# INV_Power.net
KiCad netlist of a schematic drawn in Altium Designer
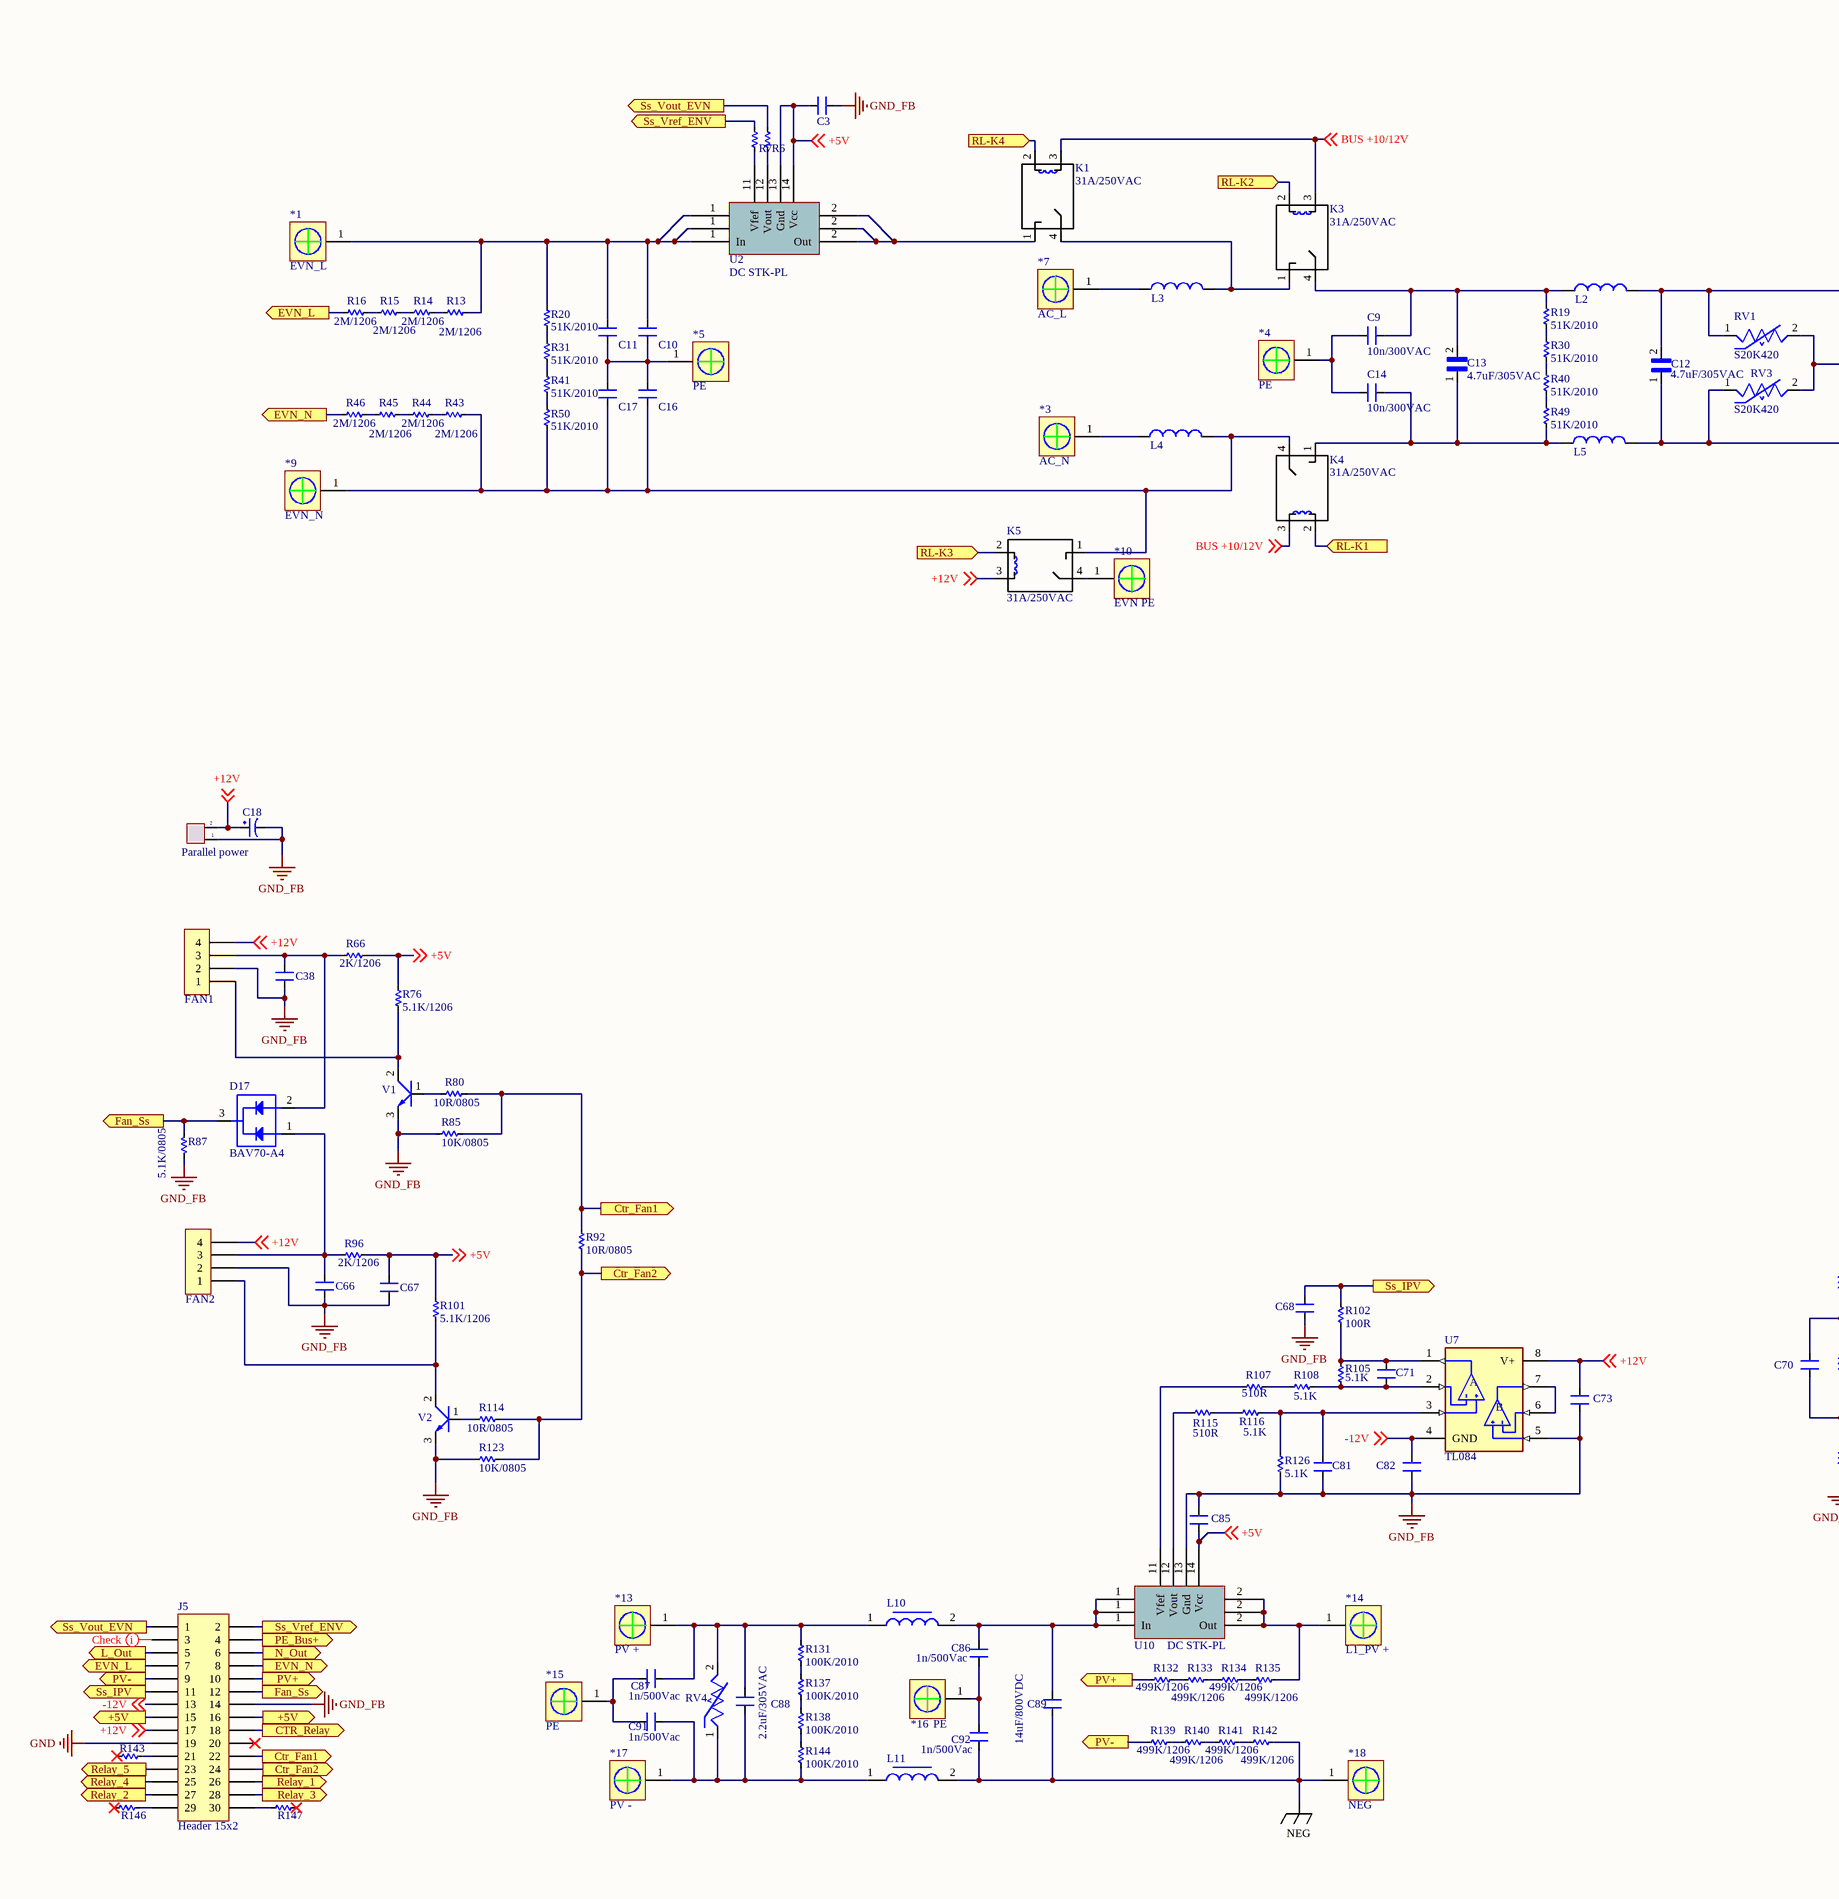
[diagram p0: INV.Power.SchDoc, left]
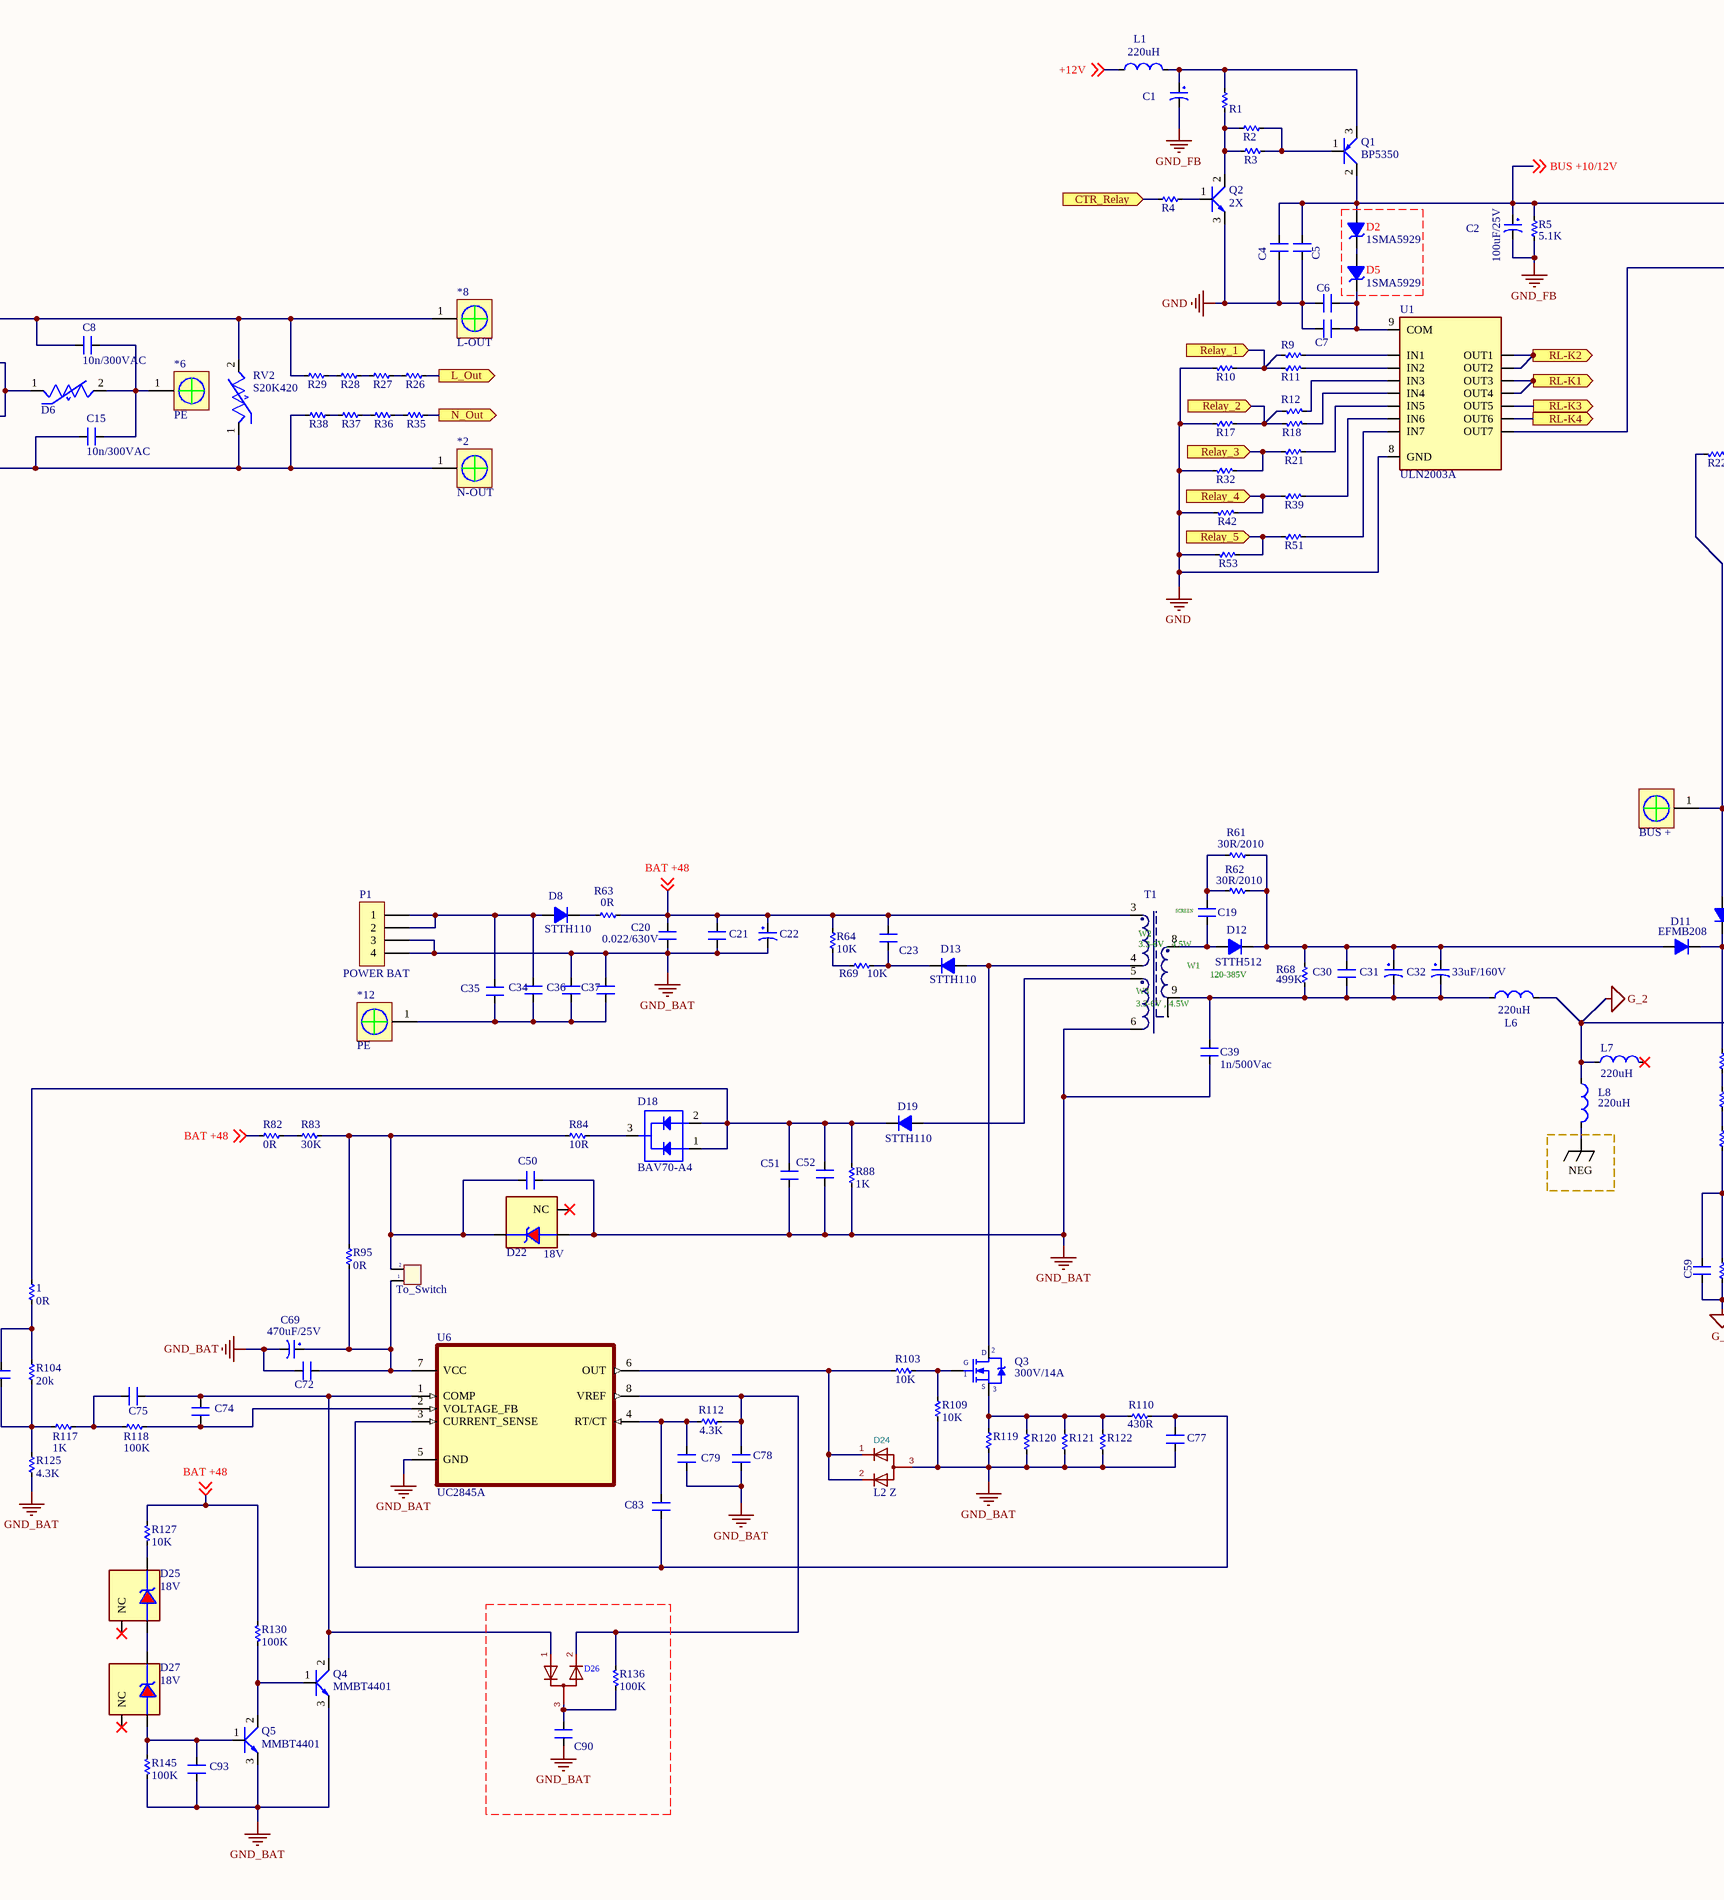
[diagram p1: INV.Power.SchDoc, middle]
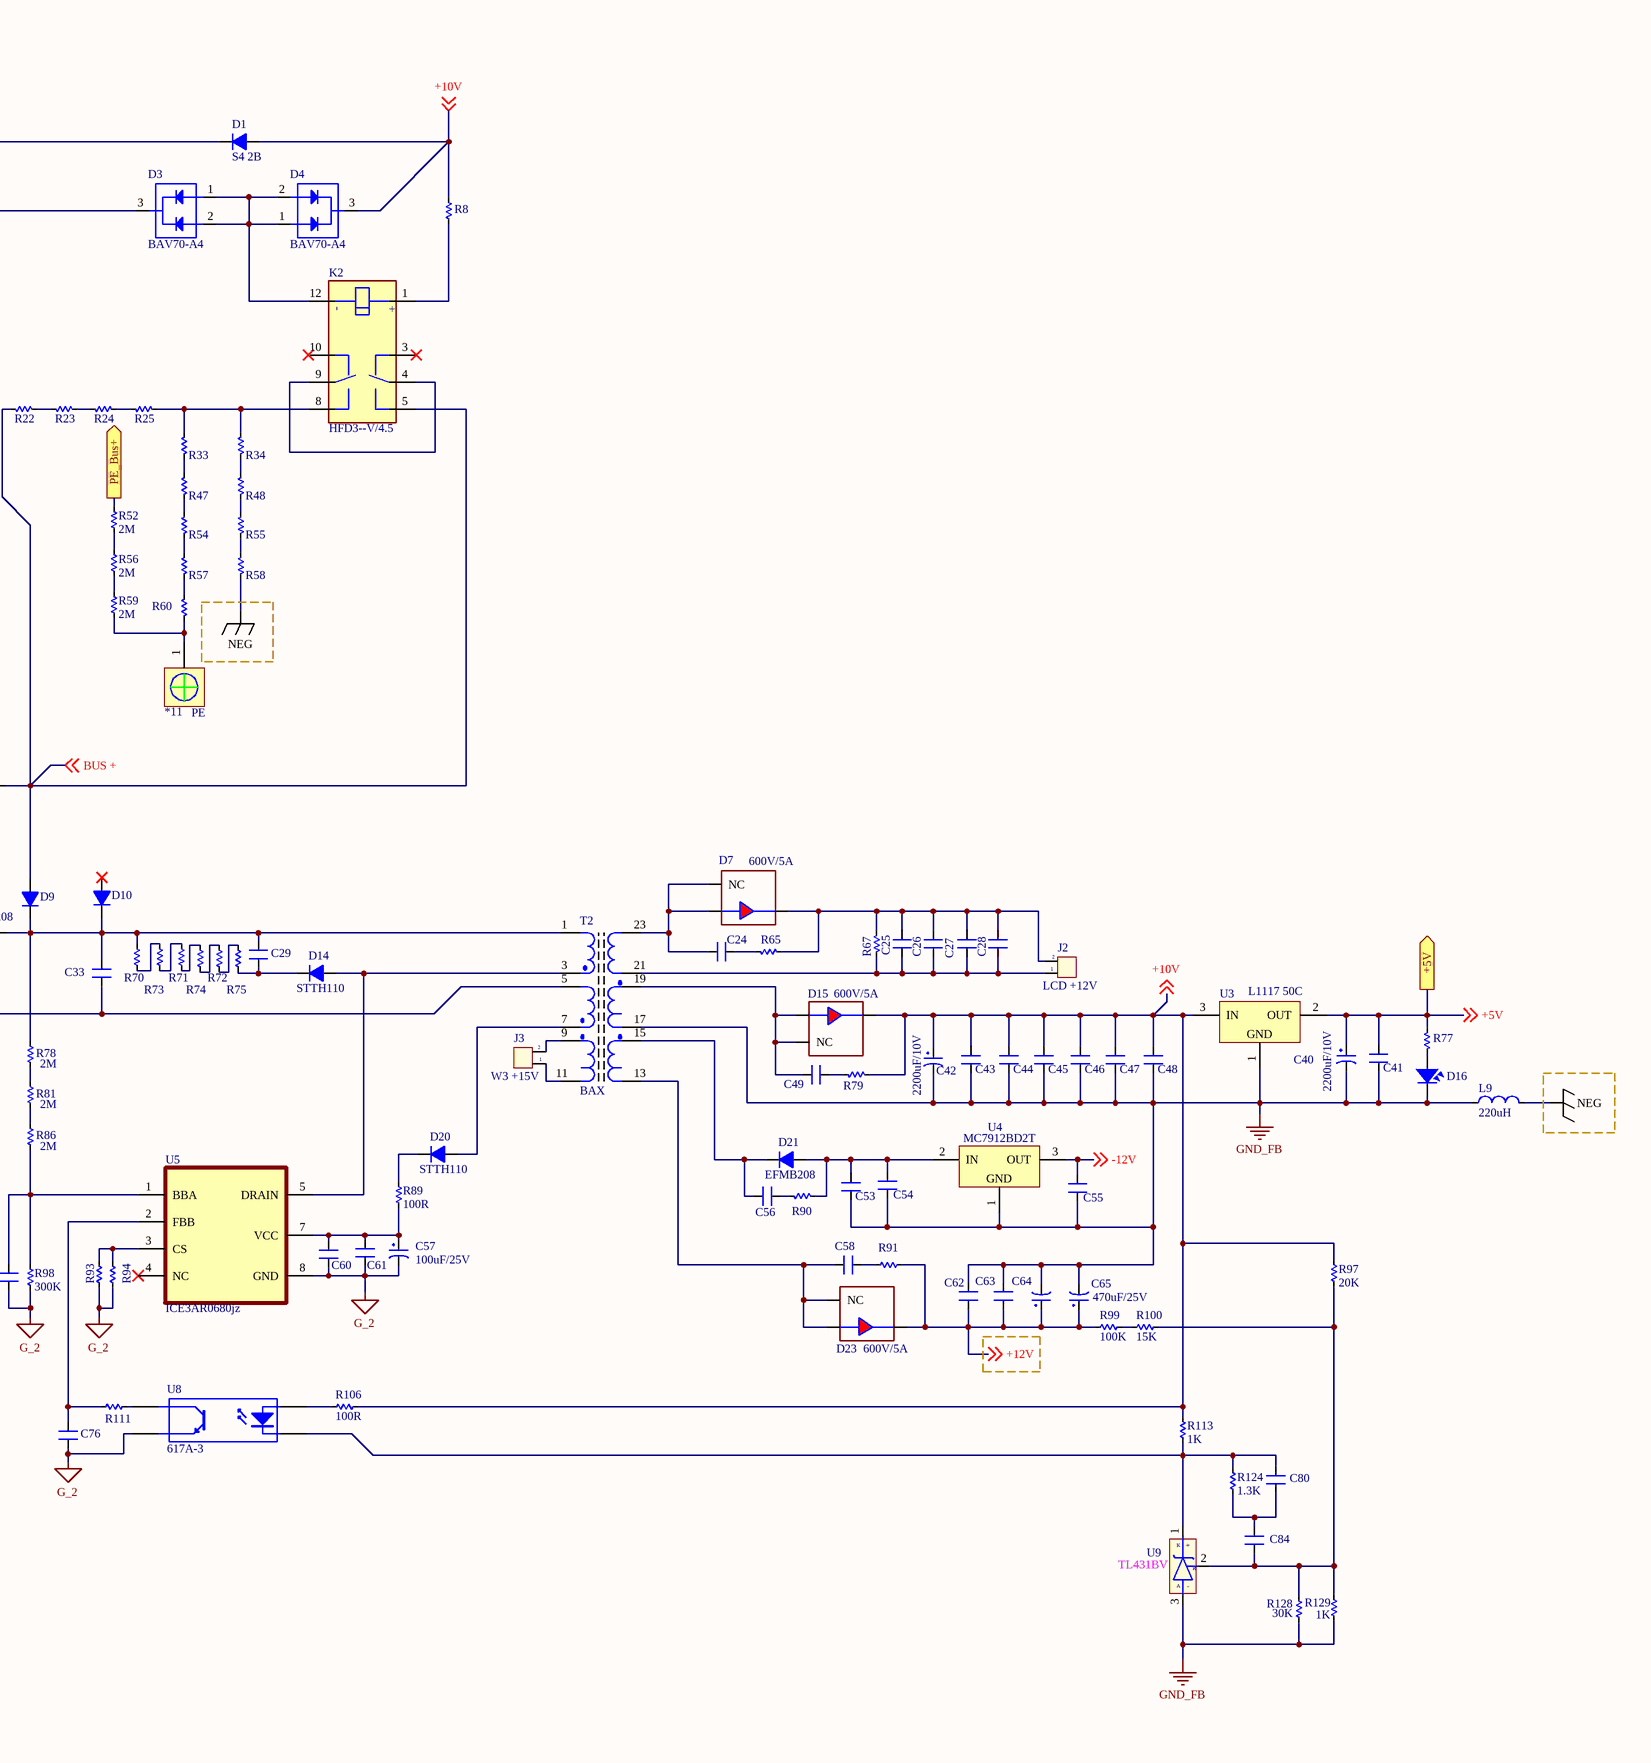
[diagram p2: INV.Power.SchDoc, right]

(export (version "E")
  (design (tool "Eeschema 10.0.6"))
  (components
    (comp (ref "*1") (value "EVN_L") (footprint "Copper Pipe") (libsource (lib "") (part "Copper_3")))
    (comp (ref "*2") (value "N-OUT") (footprint "Copper Pipe") (libsource (lib "") (part "Copper_2")))
    (comp (ref "*3") (value "AC_N") (footprint "Copper Pipe") (libsource (lib "") (part "Copper_1")))
    (comp (ref "*4") (value "PE") (footprint "Copper Pipe") (libsource (lib "") (part "Copper_1")))
    (comp (ref "*5") (value "PE") (footprint "Copper Pipe") (libsource (lib "Lib_RD_Cg") (part "Copper")))
    (comp (ref "*6") (value "PE") (footprint "Copper Pipe") (libsource (lib "") (part "Copper_2")))
    (comp (ref "*7") (value "AC_L") (footprint "Copper Pipe") (libsource (lib "") (part "Copper_1")))
    (comp (ref "*8") (value "L-OUT") (footprint "Copper Pipe") (libsource (lib "") (part "Copper_2")))
    (comp (ref "*9") (value "EVN_N") (footprint "Copper Pipe") (libsource (lib "") (part "Copper_3")))
    (comp (ref "*10")
      (value "EVN PE")
      (footprint "Copper Pipe")
      (libsource (lib "Lib_RD_Cg") (part "Copper"))
    )
    (comp (ref "*11") (value "PE") (footprint "Copper Pipe") (libsource (lib "") (part "Copper_3")))
    (comp (ref "*12") (value "PE") (footprint "Copper Pipe") (libsource (lib "") (part "Copper_1")))
    (comp (ref "*13") (value "PV +") (footprint "Copper Pipe") (libsource (lib "") (part "Copper_1")))
    (comp (ref "*14")
      (value "L1_PV +")
      (footprint "Copper Pipe")
      (libsource (lib "Lib_RD_Cg") (part "Copper"))
    )
    (comp (ref "*15") (value "PE") (footprint "Copper Pipe") (libsource (lib "") (part "Copper_1")))
    (comp (ref "*16") (value "PE") (footprint "Copper Pipe") (libsource (lib "") (part "Copper_1")))
    (comp (ref "*17") (value "PV -") (footprint "Copper Pipe") (libsource (lib "") (part "Copper_1")))
    (comp (ref "*18") (value "NEG") (footprint "Copper Pipe") (libsource (lib "Lib_RD_Cg") (part "Copper")))
    (comp (ref "1")
      (value "0R")
      (footprint "RES-SMD-0603 EX")
      (description "Resistor")
      (fields
        (field (name "MANUFACTURER") "Generic Components")
        (field (name "PUBLISHER") "Altium Hobart Technology Centre")
      )
      (libsource (lib "RAL") (part "Res-SMD"))
    )
    (comp (ref "C1")
      (value "100uF/25V")
      (footprint "CAP-10X17-N")
      (libsource (lib "Lib_RD_Cg") (part "Cap - 10x18 - N"))
    )
    (comp (ref "C2")
      (value "100uF/25V")
      (footprint "CAP-10X17-N")
      (libsource (lib "Lib_RD_Cg") (part "Cap - 10x18 - N"))
    )
    (comp (ref "C3")
      (value "10n/300VAC")
      (footprint "CAP-SMD-0805 EX")
      (description "High Voltage Ceramic Capacitors CS103M")
      (libsource (lib "RAL") (part "CAP-SMD"))
    )
    (comp (ref "C4") (value "~") (footprint "CAP-SMD-0805 EX") (libsource (lib "RAL") (part "CAP-SMD")))
    (comp (ref "C5") (value "~") (footprint "CAP-SMD-0805 EX") (libsource (lib "RAL") (part "CAP-SMD")))
    (comp (ref "C6") (value "~") (footprint "CAP-SMD-0805 EX") (libsource (lib "RAL") (part "CAP-SMD")))
    (comp (ref "C7") (value "~") (footprint "CAP-SMD-0805 EX") (libsource (lib "RAL") (part "CAP-SMD")))
    (comp (ref "C8")
      (value "10n/300VAC")
      (footprint "CAP-SMD-0805 EX")
      (description "High Voltage Ceramic Capacitors CS103M")
      (libsource (lib "RAL") (part "CAP-SMD"))
    )
    (comp (ref "C9")
      (value "10n/300VAC")
      (footprint "CAP-SMD-0805 EX")
      (description "High Voltage Ceramic Capacitors CS103M")
      (libsource (lib "RAL") (part "CAP-SMD"))
    )
    (comp (ref "C10")
      (value "10n/300VAC")
      (footprint "CAP-SMD-0805 EX")
      (description "High Voltage Ceramic Capacitors CS103M")
      (libsource (lib "RAL") (part "CAP-SMD"))
    )
    (comp (ref "C11")
      (value "10n/300VAC")
      (footprint "CAP-SMD-0805 EX")
      (description "High Voltage Ceramic Capacitors CS103M")
      (libsource (lib "RAL") (part "CAP-SMD"))
    )
    (comp (ref "C12")
      (value "4.7uF/305VAC")
      (footprint "CAPRR2250W80L2600T850H1500")
      (description "Polypropylene Film Capacitor, 305V ac, ±20%, 4.7μF")
      (fields (field (name "MP") "ECWFG2J475KA") (field (name "MF") "Panasonic"))
      (libsource (lib "Lib_RD_Cg") (part "ECWFG2J475KA"))
    )
    (comp (ref "C13")
      (value "4.7uF/305VAC")
      (footprint "CAPRR2250W80L2600T850H1500")
      (description "Polypropylene Film Capacitor, 305V ac, ±20%, 4.7μF")
      (fields (field (name "MP") "ECWFG2J475KA") (field (name "MF") "Panasonic"))
      (libsource (lib "Lib_RD_Cg") (part "ECWFG2J475KA"))
    )
    (comp (ref "C14")
      (value "10n/300VAC")
      (footprint "CAP-SMD-0805 EX")
      (description "High Voltage Ceramic Capacitors CS103M")
      (libsource (lib "RAL") (part "CAP-SMD"))
    )
    (comp (ref "C15")
      (value "10n/300VAC")
      (footprint "CAP-SMD-0805 EX")
      (description "High Voltage Ceramic Capacitors CS103M")
      (libsource (lib "RAL") (part "CAP-SMD"))
    )
    (comp (ref "C16")
      (value "10n/300VAC")
      (footprint "CAP-SMD-0805 EX")
      (description "High Voltage Ceramic Capacitors CS103M")
      (libsource (lib "RAL") (part "CAP-SMD"))
    )
    (comp (ref "C17")
      (value "10n/300VAC")
      (footprint "CAP-SMD-0805 EX")
      (description "High Voltage Ceramic Capacitors CS103M")
      (libsource (lib "RAL") (part "CAP-SMD"))
    )
    (comp (ref "C18")
      (value "470uF/25V")
      (footprint "CAP-10X17-N")
      (libsource (lib "") (part "Cap - 10x18 - N_2"))
    )
    (comp (ref "C19") (value "~") (footprint "CAP-SMD-0805 EX") (libsource (lib "RAL") (part "CAP-SMD")))
    (comp (ref "C20")
      (value "0.022/630V")
      (footprint "CAP-SMD-0805 EX")
      (description "WIMA MKS 4 Metallized Polyester (PET) Capacitors")
      (libsource (lib "RAL") (part "CAP-SMD"))
    )
    (comp (ref "C21") (value "~") (footprint "CAP-SMD-0805 EX") (libsource (lib "RAL") (part "CAP-SMD")))
    (comp (ref "C22")
      (value "27uF/100V")
      (footprint "CAP-10X17-N")
      (description "Cắm 100uF 25V")
      (libsource (lib "") (part "Cap - 10x18 - N_1"))
    )
    (comp (ref "C23") (value "~") (footprint "CAP-SMD-0805 EX") (libsource (lib "RAL") (part "CAP-SMD")))
    (comp (ref "C24") (value "~") (footprint "CAP-SMD-0805 EX") (libsource (lib "RAL") (part "CAP-SMD")))
    (comp (ref "C25")
      (value "223J630V")
      (footprint "CAP-SMD-0805 EX")
      (libsource (lib "RAL") (part "CAP-SMD"))
    )
    (comp (ref "C26")
      (value "223J630V")
      (footprint "CAP-SMD-0805 EX")
      (libsource (lib "RAL") (part "CAP-SMD"))
    )
    (comp (ref "C27")
      (value "223J630V")
      (footprint "CAP-SMD-0805 EX")
      (libsource (lib "RAL") (part "CAP-SMD"))
    )
    (comp (ref "C28")
      (value "223J630V")
      (footprint "CAP-SMD-0805 EX")
      (libsource (lib "RAL") (part "CAP-SMD"))
    )
    (comp (ref "C29")
      (value "223J630V")
      (footprint "CAP-SMD-0805 EX")
      (libsource (lib "RAL") (part "CAP-SMD"))
    )
    (comp (ref "C30") (value "~") (footprint "CAP-SMD-0805 EX") (libsource (lib "RAL") (part "CAP-SMD")))
    (comp (ref "C31")
      (value "33uF/160V")
      (footprint "CAP-10X17-N")
      (libsource (lib "") (part "Cap - 10x18 - N_1"))
    )
    (comp (ref "C32")
      (value "33uF/160V")
      (footprint "CAP-10X17-N")
      (libsource (lib "") (part "Cap - 10x18 - N_1"))
    )
    (comp (ref "C33")
      (value "2uF/600VDC")
      (footprint "CAP-SMD-0805 EX")
      (libsource (lib "RAL") (part "CAP-SMD"))
    )
    (comp (ref "C34") (value "~") (footprint "CAP-SMD-0805 EX") (libsource (lib "RAL") (part "CAP-SMD")))
    (comp (ref "C35") (value "~") (footprint "CAP-SMD-0805 EX") (libsource (lib "RAL") (part "CAP-SMD")))
    (comp (ref "C36") (value "~") (footprint "CAP-SMD-0805 EX") (libsource (lib "RAL") (part "CAP-SMD")))
    (comp (ref "C37") (value "~") (footprint "CAP-SMD-0805 EX") (libsource (lib "RAL") (part "CAP-SMD")))
    (comp (ref "C38") (value "~") (footprint "CAP-SMD-0805 EX") (libsource (lib "RAL") (part "CAP-SMD")))
    (comp (ref "C39")
      (value "1n/500Vac")
      (footprint "CAP-SMD-0805 EX")
      (libsource (lib "RAL") (part "CAP-SMD"))
    )
    (comp (ref "C40")
      (value "2200uF/10V")
      (footprint "CAP-10X17-N")
      (libsource (lib "") (part "Cap - 10x18 - N_1"))
    )
    (comp (ref "C41") (value "~") (footprint "CAP-SMD-0805 EX") (libsource (lib "RAL") (part "CAP-SMD")))
    (comp (ref "C42")
      (value "2200uF/10V")
      (footprint "CAP-10X17-N")
      (libsource (lib "") (part "Cap - 10x18 - N_1"))
    )
    (comp (ref "C43") (value "~") (footprint "CAP-SMD-0805 EX") (libsource (lib "RAL") (part "CAP-SMD")))
    (comp (ref "C44") (value "~") (footprint "CAP-SMD-0805 EX") (libsource (lib "RAL") (part "CAP-SMD")))
    (comp (ref "C45") (value "~") (footprint "CAP-SMD-0805 EX") (libsource (lib "RAL") (part "CAP-SMD")))
    (comp (ref "C46") (value "~") (footprint "CAP-SMD-0805 EX") (libsource (lib "RAL") (part "CAP-SMD")))
    (comp (ref "C47") (value "~") (footprint "CAP-SMD-0805 EX") (libsource (lib "RAL") (part "CAP-SMD")))
    (comp (ref "C48") (value "~") (footprint "CAP-SMD-0805 EX") (libsource (lib "RAL") (part "CAP-SMD")))
    (comp (ref "C49") (value "~") (footprint "CAP-SMD-0805 EX") (libsource (lib "RAL") (part "CAP-SMD")))
    (comp (ref "C50") (value "~") (footprint "CAP-SMD-0805 EX") (libsource (lib "RAL") (part "CAP-SMD")))
    (comp (ref "C51") (value "~") (footprint "CAP-SMD-0805 EX") (libsource (lib "RAL") (part "CAP-SMD")))
    (comp (ref "C52") (value "~") (footprint "CAP-SMD-0805 EX") (libsource (lib "RAL") (part "CAP-SMD")))
    (comp (ref "C53") (value "~") (footprint "CAP-SMD-0805 EX") (libsource (lib "RAL") (part "CAP-SMD")))
    (comp (ref "C54") (value "~") (footprint "CAP-SMD-0805 EX") (libsource (lib "RAL") (part "CAP-SMD")))
    (comp (ref "C55") (value "~") (footprint "CAP-SMD-0805 EX") (libsource (lib "RAL") (part "CAP-SMD")))
    (comp (ref "C56") (value "~") (footprint "CAP-SMD-0805 EX") (libsource (lib "RAL") (part "CAP-SMD")))
    (comp (ref "C57")
      (value "100uF/25V")
      (footprint "CAP-10X17-N")
      (description "Cắm 100uF 25V")
      (libsource (lib "") (part "Cap - 10x18 - N_1"))
    )
    (comp (ref "C58") (value "~") (footprint "CAP-SMD-0805 EX") (libsource (lib "RAL") (part "CAP-SMD")))
    (comp (ref "C59") (value "~") (footprint "CAP-SMD-0805 EX") (libsource (lib "RAL") (part "CAP-SMD")))
    (comp (ref "C60")
      (value "223J630V")
      (footprint "CAP-SMD-0805 EX")
      (libsource (lib "RAL") (part "CAP-SMD"))
    )
    (comp (ref "C61")
      (value "223J630V")
      (footprint "CAP-SMD-0805 EX")
      (libsource (lib "RAL") (part "CAP-SMD"))
    )
    (comp (ref "C62") (value "~") (footprint "CAP-SMD-0805 EX") (libsource (lib "RAL") (part "CAP-SMD")))
    (comp (ref "C63") (value "~") (footprint "CAP-SMD-0805 EX") (libsource (lib "RAL") (part "CAP-SMD")))
    (comp (ref "C64")
      (value "470uF/25V")
      (footprint "CAP-10X17-N")
      (libsource (lib "Lib_RD_Cg") (part "Cap - 10x18 - N"))
    )
    (comp (ref "C65")
      (value "470uF/25V")
      (footprint "CAP-10X17-N")
      (libsource (lib "Lib_RD_Cg") (part "Cap - 10x18 - N"))
    )
    (comp (ref "C66") (value "~") (footprint "CAP-SMD-0805 EX") (libsource (lib "RAL") (part "CAP-SMD")))
    (comp (ref "C67") (value "~") (footprint "CAP-SMD-0805 EX") (libsource (lib "RAL") (part "CAP-SMD")))
    (comp (ref "C68") (value "~") (footprint "CAP-SMD-0805 EX") (libsource (lib "RAL") (part "CAP-SMD")))
    (comp (ref "C69")
      (value "470uF/25V")
      (footprint "CAP-10X17-N")
      (description "Cắm 100uF 25V")
      (libsource (lib "") (part "Cap - 10x18 - N_3"))
    )
    (comp (ref "C70") (value "~") (footprint "CAP-SMD-0805 EX") (libsource (lib "RAL") (part "CAP-SMD")))
    (comp (ref "C71") (value "~") (footprint "CAP-SMD-0805 EX") (libsource (lib "RAL") (part "CAP-SMD")))
    (comp (ref "C72") (value "~") (footprint "CAP-SMD-0805 EX") (libsource (lib "RAL") (part "CAP-SMD")))
    (comp (ref "C73") (value "~") (footprint "CAP-SMD-0805 EX") (libsource (lib "RAL") (part "CAP-SMD")))
    (comp (ref "C74") (value "~") (footprint "CAP-SMD-0805 EX") (libsource (lib "RAL") (part "CAP-SMD")))
    (comp (ref "C75") (value "~") (footprint "CAP-SMD-0805 EX") (libsource (lib "RAL") (part "CAP-SMD")))
    (comp (ref "C76") (value "~") (footprint "CAP-SMD-0805 EX") (libsource (lib "RAL") (part "CAP-SMD")))
    (comp (ref "C77") (value "~") (footprint "CAP-SMD-0805 EX") (libsource (lib "RAL") (part "CAP-SMD")))
    (comp (ref "C78") (value "~") (footprint "CAP-SMD-0805 EX") (libsource (lib "RAL") (part "CAP-SMD")))
    (comp (ref "C79") (value "~") (footprint "CAP-SMD-0805 EX") (libsource (lib "RAL") (part "CAP-SMD")))
    (comp (ref "C80") (value "~") (footprint "CAP-SMD-0805 EX") (libsource (lib "RAL") (part "CAP-SMD")))
    (comp (ref "C81") (value "~") (footprint "CAP-SMD-0805 EX") (libsource (lib "RAL") (part "CAP-SMD")))
    (comp (ref "C82") (value "~") (footprint "CAP-SMD-0805 EX") (libsource (lib "RAL") (part "CAP-SMD")))
    (comp (ref "C83") (value "~") (footprint "CAP-SMD-0805 EX") (libsource (lib "RAL") (part "CAP-SMD")))
    (comp (ref "C84") (value "~") (footprint "CAP-SMD-0805 EX") (libsource (lib "RAL") (part "CAP-SMD")))
    (comp (ref "C85") (value "~") (footprint "CAP-SMD-0805 EX") (libsource (lib "RAL") (part "CAP-SMD")))
    (comp (ref "C86")
      (value "1n/500Vac")
      (footprint "CAP-SMD-0805 EX")
      (libsource (lib "RAL") (part "CAP-SMD"))
    )
    (comp (ref "C87")
      (value "1n/500Vac")
      (footprint "CAP-SMD-0805 EX")
      (libsource (lib "RAL") (part "CAP-SMD"))
    )
    (comp (ref "C88")
      (value "2.2uF/305VAC")
      (footprint "CAP-SMD-0805 EX")
      (libsource (lib "RAL") (part "CAP-SMD"))
    )
    (comp (ref "C89")
      (value "14uF/800VDC")
      (footprint "CAP-SMD-0805 EX")
      (libsource (lib "RAL") (part "CAP-SMD"))
    )
    (comp (ref "C90") (value "~") (footprint "CAP-SMD-0805 EX") (libsource (lib "RAL") (part "CAP-SMD")))
    (comp (ref "C91")
      (value "1n/500Vac")
      (footprint "CAP-SMD-0805 EX")
      (libsource (lib "RAL") (part "CAP-SMD"))
    )
    (comp (ref "C92")
      (value "1n/500Vac")
      (footprint "CAP-SMD-0805 EX")
      (libsource (lib "RAL") (part "CAP-SMD"))
    )
    (comp (ref "C93") (value "~") (footprint "CAP-SMD-0805 EX") (libsource (lib "RAL") (part "CAP-SMD")))
    (comp (ref "D1") (value "S4 2B") (footprint "1N4148") (libsource (lib "Lib_RD_Cg") (part "DIODE")))
    (comp (ref "D2")
      (value "1SMA5929")
      (footprint "DIODE ZENNER SOD123 *")
      (description "Diode Zenner 15V")
      (libsource (lib "Lib_RD_Cg") (part "DIODE ZENNER"))
    )
    (comp (ref "D3")
      (value "BAV70-A4")
      (footprint "DIO_STTH2003CG-TR")
      (fields (field (name "MP") "STTH2003CG-TR"))
      (libsource (lib "Lib_RD_Cg") (part "Diode Double"))
    )
    (comp (ref "D4")
      (value "BAV70-A4")
      (footprint "DIO_STTH2003CG-TR")
      (fields (field (name "MP") "STTH2003CG-TR"))
      (libsource (lib "Lib_RD_Cg") (part "Diode Double"))
    )
    (comp (ref "D5")
      (value "1SMA5929")
      (footprint "DIODE ZENNER SOD123 *")
      (description "Diode Zenner 15V")
      (libsource (lib "Lib_RD_Cg") (part "DIODE ZENNER"))
    )
    (comp (ref "D6")
      (value "EPCOS")
      (footprint "VAR_B72220S0301K101")
      (description "Chống sét lan truyền B88069X4880S102(ví dụ)")
      (fields (field (name "MP") "B72220S0301K101") (field (name "MF") "TDK"))
      (libsource (lib "Lib_RD_Cg") (part "Varistor B772"))
    )
    (comp (ref "D7")
      (value "600V/5A")
      (footprint "SOT95P237X112-3N")
      (description "600V/5A Diode SHHT 506B")
      (fields (field (name "MF") "ON Semiconductor") (field (name "MP") "BZX84-C7V5"))
      (libsource (lib "Lib_RD_Cg") (part "Diode SHHT 506B"))
    )
    (comp (ref "D8")
      (value "STTH110")
      (footprint "1N4148")
      (description "Diode 1000V/1A SMB")
      (libsource (lib "Lib_RD_Cg") (part "DIODE"))
    )
    (comp (ref "D9")
      (value "EFMB208")
      (footprint "1N4148")
      (description "Diode 600V/2A SMB thay the ES2J")
      (libsource (lib "Lib_RD_Cg") (part "DIODE"))
    )
    (comp (ref "D10")
      (value "EFMB208")
      (footprint "1N4148")
      (description "Diode 600V/2A SMB thay the ES2J")
      (libsource (lib "Lib_RD_Cg") (part "DIODE"))
    )
    (comp (ref "D11")
      (value "EFMB208")
      (footprint "1N4148")
      (description "Diode 600V/2A SMB thay the ES2J")
      (libsource (lib "Lib_RD_Cg") (part "DIODE"))
    )
    (comp (ref "D12")
      (value "STTH512")
      (footprint "1N4148")
      (description "Diode 1200V/5A")
      (libsource (lib "Lib_RD_Cg") (part "DIODE"))
    )
    (comp (ref "D13")
      (value "STTH110")
      (footprint "1N4148")
      (description "Diode 1000V/1A SMB")
      (libsource (lib "Lib_RD_Cg") (part "DIODE"))
    )
    (comp (ref "D14")
      (value "STTH110")
      (footprint "1N4148")
      (description "Diode 1000V/1A SMB")
      (libsource (lib "Lib_RD_Cg") (part "DIODE"))
    )
    (comp (ref "D15")
      (value "600V/5A")
      (footprint "SOT95P237X112-3N")
      (description "600V/5A Diode SHHT 506B")
      (fields (field (name "MF") "ON Semiconductor") (field (name "MP") "BZX84-C7V5"))
      (libsource (lib "") (part "Diode SHHT 506B_1"))
    )
    (comp (ref "D16")
      (value "LED")
      (footprint "LED 2835 NEW")
      (description "LED Single colour Green and Red")
      (libsource (lib "Lib_RD_Cg") (part "LED"))
    )
    (comp (ref "D17")
      (value "BAV70-A4")
      (footprint "DIO_STTH2003CG-TR")
      (fields (field (name "MP") "STTH2003CG-TR"))
      (libsource (lib "Lib_RD_Cg") (part "Diode Double"))
    )
    (comp (ref "D18")
      (value "BAV70-A4")
      (footprint "DIO_STTH2003CG-TR")
      (fields (field (name "MP") "STTH2003CG-TR"))
      (libsource (lib "Lib_RD_Cg") (part "Diode Double"))
    )
    (comp (ref "D19")
      (value "STTH110")
      (footprint "1N4148")
      (description "Diode 1000V/1A SMB")
      (libsource (lib "Lib_RD_Cg") (part "DIODE"))
    )
    (comp (ref "D20")
      (value "STTH110")
      (footprint "1N4148")
      (description "Diode 1000V/1A SMB")
      (libsource (lib "Lib_RD_Cg") (part "DIODE"))
    )
    (comp (ref "D21")
      (value "EFMB208")
      (footprint "1N4148")
      (description "Diode 600V/2A SMB thay the ES2J")
      (libsource (lib "Lib_RD_Cg") (part "DIODE"))
    )
    (comp (ref "D22")
      (value "18V")
      (footprint "SOT95P237X112-3N")
      (description "BZX84-C18(Y6W) Zenner 18V thay the BZT52C18")
      (fields (field (name "MF") "ON Semiconductor") (field (name "MP") "BZX84-C7V5"))
      (libsource (lib "") (part "Diode Zener Sot-95_1"))
    )
    (comp (ref "D23")
      (value "600V/5A")
      (footprint "SOT95P237X112-3N")
      (description "600V/5A Diode SHHT 506B")
      (fields (field (name "MF") "ON Semiconductor") (field (name "MP") "BZX84-C7V5"))
      (libsource (lib "Lib_RD_Cg") (part "Diode SHHT 506B"))
    )
    (comp (ref "D24")
      (value "L2 Z")
      (footprint "SOT-23")
      (description "LBAS40-06LT1G\r\n S-LBAS40-06LT1G")
      (libsource (lib "Lib_RD_Cg") (part "Dual-Diode_CA"))
    )
    (comp (ref "D25")
      (value "18V")
      (footprint "SOT95P237X112-3N")
      (description "BZX84-C18(Y6W) Zenner 18V thay the BZT52C18")
      (fields (field (name "MF") "ON Semiconductor") (field (name "MP") "BZX84-C7V5"))
      (libsource (lib "Lib_RD_Cg") (part "Diode Zener Sot-95"))
    )
    (comp (ref "D26")
      (value "Dual-Diode_CA_1")
      (footprint "SOT-23")
      (description "BAT54S(D88) thay the BAV99:A7")
      (libsource (lib "Lib_RD_Cg") (part "Dual-Diode_CA_1"))
    )
    (comp (ref "D27")
      (value "18V")
      (footprint "SOT95P237X112-3N")
      (description "BZX84-C18(Y6W) Zenner 18V thay the BZT52C18")
      (fields (field (name "MF") "ON Semiconductor") (field (name "MP") "BZX84-C7V5"))
      (libsource (lib "Lib_RD_Cg") (part "Diode Zener Sot-95"))
    )
    (comp (ref "H1")
      (value "FAN1")
      (footprint "XH2.54M-4")
      (description "Cắm")
      (libsource (lib "Altium_Lib_by_KhueNguyenCreator") (part "Header 4P 2.54 Duc Thang"))
    )
    (comp (ref "H2")
      (value "FAN2")
      (footprint "XH2.54M-4")
      (description "Cắm")
      (libsource (lib "Altium_Lib_by_KhueNguyenCreator") (part "Header 4P 2.54 Duc Thang"))
    )
    (comp (ref "J1") (value "Parallel power") (footprint "Jump2") (libsource (lib "AE_RD") (part "Jump2")))
    (comp (ref "J2") (value "LCD +12V") (footprint "Jump2") (libsource (lib "") (part "Jump2_1")))
    (comp (ref "J3") (value "W3 +15V") (footprint "Jump2") (libsource (lib "AE_RD") (part "Jump2")))
    (comp (ref "J4") (value "To_Switch") (footprint "Jump2") (libsource (lib "") (part "Jump2_1")))
    (comp (ref "J5")
      (value "Header 15x2")
      (footprint "Head 1X16 - CAI THANG")
      (description "Header, 15x2-Pin 2.5mm")
      (fields (field (name "PUBLISHER") "Altium Limited"))
      (libsource (lib "Lib_RD_Cg") (part "Header 15x2"))
    )
    (comp (ref "K1")
      (value "31A/250VAC")
      (footprint "RELAY 10A/250V")
      (description "HF161F-W 12-HT(477)")
      (libsource (lib "Lib_RD_Cg") (part "RELAY 10A/250V-HF"))
    )
    (comp (ref "K2")
      (value "HFD3--V/4.5")
      (footprint "HFD3")
      (fields (field (name "MF") "Hongfa") (field (name "MP") "HFD3/012-L2"))
      (libsource (lib "Lib_RD_Cg") (part "HFD3--V/4.5"))
    )
    (comp (ref "K3")
      (value "31A/250VAC")
      (footprint "RELAY 10A/250V")
      (description "HF161F-W 12-HT(477)")
      (libsource (lib "Lib_RD_Cg") (part "RELAY 10A/250V-HF"))
    )
    (comp (ref "K4")
      (value "31A/250VAC")
      (footprint "RELAY 10A/250V")
      (description "HF161F-W 12-HT(477)")
      (libsource (lib "Lib_RD_Cg") (part "RELAY 10A/250V-HF"))
    )
    (comp (ref "K5")
      (value "31A/250VAC")
      (footprint "RELAY 10A/250V")
      (description "HF161F-W 12-HT(477)")
      (libsource (lib "") (part "RELAY 10A/250V-HF_1"))
    )
    (comp (ref "L1")
      (value "220uH")
      (footprint "CUON LOC 1010")
      (description "Inductor")
      (libsource (lib "") (part "L1_1"))
    )
    (comp (ref "L2")
      (value "Cuộn L")
      (footprint "IND_1210")
      (description "Fixed Inductors 18uH 10% 2.52MHz")
      (fields
        (field (name "MANUFACTURER") "Wurth Electronics")
        (field (name "MANUFACTURER PART NUMBER") "CMH322522-180KL")
      )
      (libsource (lib "Altium_Lib_by_KhueNguyenCreator") (part "IND_18uH-0.12A-10%-SMD"))
    )
    (comp (ref "L3")
      (value "Cuộn L")
      (footprint "IND_1210")
      (description "Fixed Inductors 18uH 10% 2.52MHz")
      (fields
        (field (name "MANUFACTURER") "Wurth Electronics")
        (field (name "MANUFACTURER PART NUMBER") "CMH322522-180KL")
      )
      (libsource (lib "Altium_Lib_by_KhueNguyenCreator") (part "IND_18uH-0.12A-10%-SMD"))
    )
    (comp (ref "L4")
      (value "Cuộn L")
      (footprint "IND_1210")
      (description "Fixed Inductors 18uH 10% 2.52MHz")
      (fields
        (field (name "MANUFACTURER") "Wurth Electronics")
        (field (name "MANUFACTURER PART NUMBER") "CMH322522-180KL")
      )
      (libsource (lib "Altium_Lib_by_KhueNguyenCreator") (part "IND_18uH-0.12A-10%-SMD"))
    )
    (comp (ref "L5")
      (value "Cuộn L")
      (footprint "IND_1210")
      (description "Fixed Inductors 18uH 10% 2.52MHz")
      (fields
        (field (name "MANUFACTURER") "Wurth Electronics")
        (field (name "MANUFACTURER PART NUMBER") "CMH322522-180KL")
      )
      (libsource (lib "Altium_Lib_by_KhueNguyenCreator") (part "IND_18uH-0.12A-10%-SMD"))
    )
    (comp (ref "L6")
      (value "220uH")
      (footprint "CUON LOC 1010")
      (description "Inductor")
      (libsource (lib "") (part "L1_1"))
    )
    (comp (ref "L7")
      (value "220uH")
      (footprint "CUON LOC 1010")
      (description "Inductor")
      (libsource (lib "Lib_RD_Cg") (part "L1"))
    )
    (comp (ref "L8")
      (value "220uH")
      (footprint "CUON LOC 1010")
      (description "Inductor")
      (libsource (lib "Lib_RD_Cg") (part "L1"))
    )
    (comp (ref "L9")
      (value "220uH")
      (footprint "CUON LOC 1010")
      (description "Inductor")
      (libsource (lib "") (part "L1_1"))
    )
    (comp (ref "L10")
      (value "L")
      (footprint "Cuan Cam PWM Hybrid")
      (description "Cuận cảm bộ sạc PWM Hybrid")
      (fields (field (name "DESIGNED BY") "VanDungEvn"))
      (libsource (lib "Lib_RD_Cg") (part "CUON CAM PWM Hybrid"))
    )
    (comp (ref "L11")
      (value "L")
      (footprint "Cuan Cam PWM Hybrid")
      (description "Cuận cảm bộ sạc PWM Hybrid")
      (fields (field (name "DESIGNED BY") "VanDungEvn"))
      (libsource (lib "Lib_RD_Cg") (part "CUON CAM PWM Hybrid"))
    )
    (comp (ref "P1")
      (value "POWER BAT")
      (footprint "XH2.54M-4")
      (description "Cắm")
      (libsource (lib "") (part "Header 4P 2.54 Duc Thang_1"))
    )
    (comp (ref "PV +1") (value "BUS +") (footprint "Copper Pipe") (libsource (lib "") (part "Copper_1")))
    (comp (ref "Q1")
      (value "BP5350")
      (footprint "QTO-92")
      (description "thay the B772")
      (libsource (lib "Lib_RD_Cg") (part "B772M-PNP"))
    )
    (comp (ref "Q2")
      (value "2X")
      (description "thay the MMPT2222 40V/06A")
      (libsource (lib "Lib_RD_Cg") (part "D882M"))
    )
    (comp (ref "Q3")
      (value "300V/14A")
      (footprint "TO220H1")
      (description "14N30")
      (libsource (lib "RAL") (part "MOSFET IRF N"))
    )
    (comp (ref "Q4") (value "MMBT4401") (description "NPN") (libsource (lib "Lib_RD_Cg") (part "D882M")))
    (comp (ref "Q5") (value "MMBT4401") (description "NPN") (libsource (lib "Lib_RD_Cg") (part "D882M")))
    (comp (ref "R1")
      (value "10K")
      (footprint "RES-SMD-0603 EX")
      (description "Resistor")
      (fields
        (field (name "MANUFACTURER") "Generic Components")
        (field (name "PUBLISHER") "Altium Hobart Technology Centre")
      )
      (libsource (lib "RAL") (part "Res-SMD"))
    )
    (comp (ref "R2")
      (value "2K")
      (footprint "RES-SMD-0603 EX")
      (description "Resistor")
      (fields
        (field (name "MANUFACTURER") "Generic Components")
        (field (name "PUBLISHER") "Altium Hobart Technology Centre")
      )
      (libsource (lib "RAL") (part "Res-SMD"))
    )
    (comp (ref "R3")
      (value "2K")
      (footprint "RES-SMD-0603 EX")
      (description "Resistor")
      (fields
        (field (name "MANUFACTURER") "Generic Components")
        (field (name "PUBLISHER") "Altium Hobart Technology Centre")
      )
      (libsource (lib "RAL") (part "Res-SMD"))
    )
    (comp (ref "R4")
      (value "20K")
      (footprint "RES-SMD-0603 EX")
      (description "Resistor")
      (fields
        (field (name "MANUFACTURER") "Generic Components")
        (field (name "PUBLISHER") "Altium Hobart Technology Centre")
      )
      (libsource (lib "RAL") (part "Res-SMD"))
    )
    (comp (ref "R5")
      (value "5.1K")
      (footprint "RES-SMD-0603 EX")
      (description "Resistor")
      (fields
        (field (name "MANUFACTURER") "Generic Components")
        (field (name "PUBLISHER") "Altium Hobart Technology Centre")
      )
      (libsource (lib "RAL") (part "Res-SMD"))
    )
    (comp (ref "R6")
      (value "1K/0603")
      (footprint "RES-SMD-0603 EX")
      (description "Resistor")
      (fields
        (field (name "MANUFACTURER") "Generic Components")
        (field (name "PUBLISHER") "Altium Hobart Technology Centre")
      )
      (libsource (lib "RAL") (part "Res-SMD"))
    )
    (comp (ref "R7")
      (value "1K/0603")
      (footprint "RES-SMD-0603 EX")
      (description "Resistor")
      (fields
        (field (name "MANUFACTURER") "Generic Components")
        (field (name "PUBLISHER") "Altium Hobart Technology Centre")
      )
      (libsource (lib "RAL") (part "Res-SMD"))
    )
    (comp (ref "R8")
      (value "51R")
      (footprint "RES-SMD-0603 EX")
      (description "Resistor")
      (fields
        (field (name "MANUFACTURER") "Generic Components")
        (field (name "PUBLISHER") "Altium Hobart Technology Centre")
      )
      (libsource (lib "RAL") (part "Res-SMD"))
    )
    (comp (ref "R9")
      (value "10R")
      (footprint "RES-SMD-0603 EX")
      (description "Resistor")
      (fields
        (field (name "MANUFACTURER") "Generic Components")
        (field (name "PUBLISHER") "Altium Hobart Technology Centre")
      )
      (libsource (lib "RAL") (part "Res-SMD"))
    )
    (comp (ref "R10")
      (value "5.1K")
      (footprint "RES-SMD-0603 EX")
      (description "Resistor")
      (fields
        (field (name "MANUFACTURER") "Generic Components")
        (field (name "PUBLISHER") "Altium Hobart Technology Centre")
      )
      (libsource (lib "RAL") (part "Res-SMD"))
    )
    (comp (ref "R11")
      (value "10R")
      (footprint "RES-SMD-0603 EX")
      (description "Resistor")
      (fields
        (field (name "MANUFACTURER") "Generic Components")
        (field (name "PUBLISHER") "Altium Hobart Technology Centre")
      )
      (libsource (lib "RAL") (part "Res-SMD"))
    )
    (comp (ref "R12")
      (value "10R")
      (footprint "RES-SMD-0603 EX")
      (description "Resistor")
      (fields
        (field (name "MANUFACTURER") "Generic Components")
        (field (name "PUBLISHER") "Altium Hobart Technology Centre")
      )
      (libsource (lib "RAL") (part "Res-SMD"))
    )
    (comp (ref "R13")
      (value "2M/1206")
      (footprint "RES-SMD-0603 EX")
      (description "Resistor")
      (fields
        (field (name "MANUFACTURER") "Generic Components")
        (field (name "PUBLISHER") "Altium Hobart Technology Centre")
      )
      (libsource (lib "RAL") (part "Res-SMD"))
    )
    (comp (ref "R14")
      (value "2M/1206")
      (footprint "RES-SMD-0603 EX")
      (description "Resistor")
      (fields
        (field (name "MANUFACTURER") "Generic Components")
        (field (name "PUBLISHER") "Altium Hobart Technology Centre")
      )
      (libsource (lib "RAL") (part "Res-SMD"))
    )
    (comp (ref "R15")
      (value "2M/1206")
      (footprint "RES-SMD-0603 EX")
      (description "Resistor")
      (fields
        (field (name "MANUFACTURER") "Generic Components")
        (field (name "PUBLISHER") "Altium Hobart Technology Centre")
      )
      (libsource (lib "RAL") (part "Res-SMD"))
    )
    (comp (ref "R16")
      (value "2M/1206")
      (footprint "RES-SMD-0603 EX")
      (description "Resistor")
      (fields
        (field (name "MANUFACTURER") "Generic Components")
        (field (name "PUBLISHER") "Altium Hobart Technology Centre")
      )
      (libsource (lib "RAL") (part "Res-SMD"))
    )
    (comp (ref "R17")
      (value "5.1K")
      (footprint "RES-SMD-0603 EX")
      (description "Resistor")
      (fields
        (field (name "MANUFACTURER") "Generic Components")
        (field (name "PUBLISHER") "Altium Hobart Technology Centre")
      )
      (libsource (lib "RAL") (part "Res-SMD"))
    )
    (comp (ref "R18")
      (value "10R")
      (footprint "RES-SMD-0603 EX")
      (description "Resistor")
      (fields
        (field (name "MANUFACTURER") "Generic Components")
        (field (name "PUBLISHER") "Altium Hobart Technology Centre")
      )
      (libsource (lib "RAL") (part "Res-SMD"))
    )
    (comp (ref "R19")
      (value "51K/2010")
      (footprint "RES-SMD-0603 EX")
      (description "Resistor")
      (fields
        (field (name "MANUFACTURER") "Generic Components")
        (field (name "PUBLISHER") "Altium Hobart Technology Centre")
      )
      (libsource (lib "RAL") (part "Res-SMD"))
    )
    (comp (ref "R20")
      (value "51K/2010")
      (footprint "RES-SMD-0603 EX")
      (description "Resistor")
      (fields
        (field (name "MANUFACTURER") "Generic Components")
        (field (name "PUBLISHER") "Altium Hobart Technology Centre")
      )
      (libsource (lib "RAL") (part "Res-SMD"))
    )
    (comp (ref "R21")
      (value "10R")
      (footprint "RES-SMD-0603 EX")
      (description "Resistor")
      (fields
        (field (name "MANUFACTURER") "Generic Components")
        (field (name "PUBLISHER") "Altium Hobart Technology Centre")
      )
      (libsource (lib "RAL") (part "Res-SMD"))
    )
    (comp (ref "R22")
      (value "499K")
      (footprint "RES-SMD-0603 EX")
      (description "Resistor")
      (fields
        (field (name "MANUFACTURER") "Generic Components")
        (field (name "PUBLISHER") "Altium Hobart Technology Centre")
      )
      (libsource (lib "RAL") (part "Res-SMD"))
    )
    (comp (ref "R23")
      (value "499K")
      (footprint "RES-SMD-0603 EX")
      (description "Resistor")
      (fields
        (field (name "MANUFACTURER") "Generic Components")
        (field (name "PUBLISHER") "Altium Hobart Technology Centre")
      )
      (libsource (lib "RAL") (part "Res-SMD"))
    )
    (comp (ref "R24")
      (value "499K")
      (footprint "RES-SMD-0603 EX")
      (description "Resistor")
      (fields
        (field (name "MANUFACTURER") "Generic Components")
        (field (name "PUBLISHER") "Altium Hobart Technology Centre")
      )
      (libsource (lib "RAL") (part "Res-SMD"))
    )
    (comp (ref "R25")
      (value "499K")
      (footprint "RES-SMD-0603 EX")
      (description "Resistor")
      (fields
        (field (name "MANUFACTURER") "Generic Components")
        (field (name "PUBLISHER") "Altium Hobart Technology Centre")
      )
      (libsource (lib "RAL") (part "Res-SMD"))
    )
    (comp (ref "R26")
      (value "2M/1206")
      (footprint "RES-SMD-0603 EX")
      (description "Resistor")
      (fields
        (field (name "MANUFACTURER") "Generic Components")
        (field (name "PUBLISHER") "Altium Hobart Technology Centre")
      )
      (libsource (lib "RAL") (part "Res-SMD"))
    )
    (comp (ref "R27")
      (value "2M/1206")
      (footprint "RES-SMD-0603 EX")
      (description "Resistor")
      (fields
        (field (name "MANUFACTURER") "Generic Components")
        (field (name "PUBLISHER") "Altium Hobart Technology Centre")
      )
      (libsource (lib "RAL") (part "Res-SMD"))
    )
    (comp (ref "R28")
      (value "2M/1206")
      (footprint "RES-SMD-0603 EX")
      (description "Resistor")
      (fields
        (field (name "MANUFACTURER") "Generic Components")
        (field (name "PUBLISHER") "Altium Hobart Technology Centre")
      )
      (libsource (lib "RAL") (part "Res-SMD"))
    )
    (comp (ref "R29")
      (value "2M/1206")
      (footprint "RES-SMD-0603 EX")
      (description "Resistor")
      (fields
        (field (name "MANUFACTURER") "Generic Components")
        (field (name "PUBLISHER") "Altium Hobart Technology Centre")
      )
      (libsource (lib "RAL") (part "Res-SMD"))
    )
    (comp (ref "R30")
      (value "51K/2010")
      (footprint "RES-SMD-0603 EX")
      (description "Resistor")
      (fields
        (field (name "MANUFACTURER") "Generic Components")
        (field (name "PUBLISHER") "Altium Hobart Technology Centre")
      )
      (libsource (lib "RAL") (part "Res-SMD"))
    )
    (comp (ref "R31")
      (value "51K/2010")
      (footprint "RES-SMD-0603 EX")
      (description "Resistor")
      (fields
        (field (name "MANUFACTURER") "Generic Components")
        (field (name "PUBLISHER") "Altium Hobart Technology Centre")
      )
      (libsource (lib "RAL") (part "Res-SMD"))
    )
    (comp (ref "R32")
      (value "5.1K")
      (footprint "RES-SMD-0603 EX")
      (description "Resistor")
      (fields
        (field (name "MANUFACTURER") "Generic Components")
        (field (name "PUBLISHER") "Altium Hobart Technology Centre")
      )
      (libsource (lib "RAL") (part "Res-SMD"))
    )
    (comp (ref "R33")
      (value "200K")
      (footprint "RES-SMD-0603 EX")
      (description "Resistor")
      (fields
        (field (name "MANUFACTURER") "Generic Components")
        (field (name "PUBLISHER") "Altium Hobart Technology Centre")
      )
      (libsource (lib "RAL") (part "Res-SMD"))
    )
    (comp (ref "R34")
      (value "499K")
      (footprint "RES-SMD-0603 EX")
      (description "Resistor")
      (fields
        (field (name "MANUFACTURER") "Generic Components")
        (field (name "PUBLISHER") "Altium Hobart Technology Centre")
      )
      (libsource (lib "RAL") (part "Res-SMD"))
    )
    (comp (ref "R35")
      (value "2M/1206")
      (footprint "RES-SMD-0603 EX")
      (description "Resistor")
      (fields
        (field (name "MANUFACTURER") "Generic Components")
        (field (name "PUBLISHER") "Altium Hobart Technology Centre")
      )
      (libsource (lib "RAL") (part "Res-SMD"))
    )
    (comp (ref "R36")
      (value "2M/1206")
      (footprint "RES-SMD-0603 EX")
      (description "Resistor")
      (fields
        (field (name "MANUFACTURER") "Generic Components")
        (field (name "PUBLISHER") "Altium Hobart Technology Centre")
      )
      (libsource (lib "RAL") (part "Res-SMD"))
    )
    (comp (ref "R37")
      (value "2M/1206")
      (footprint "RES-SMD-0603 EX")
      (description "Resistor")
      (fields
        (field (name "MANUFACTURER") "Generic Components")
        (field (name "PUBLISHER") "Altium Hobart Technology Centre")
      )
      (libsource (lib "RAL") (part "Res-SMD"))
    )
    (comp (ref "R38")
      (value "2M/1206")
      (footprint "RES-SMD-0603 EX")
      (description "Resistor")
      (fields
        (field (name "MANUFACTURER") "Generic Components")
        (field (name "PUBLISHER") "Altium Hobart Technology Centre")
      )
      (libsource (lib "RAL") (part "Res-SMD"))
    )
    (comp (ref "R39")
      (value "10R")
      (footprint "RES-SMD-0603 EX")
      (description "Resistor")
      (fields
        (field (name "MANUFACTURER") "Generic Components")
        (field (name "PUBLISHER") "Altium Hobart Technology Centre")
      )
      (libsource (lib "RAL") (part "Res-SMD"))
    )
    (comp (ref "R40")
      (value "51K/2010")
      (footprint "RES-SMD-0603 EX")
      (description "Resistor")
      (fields
        (field (name "MANUFACTURER") "Generic Components")
        (field (name "PUBLISHER") "Altium Hobart Technology Centre")
      )
      (libsource (lib "RAL") (part "Res-SMD"))
    )
    (comp (ref "R41")
      (value "51K/2010")
      (footprint "RES-SMD-0603 EX")
      (description "Resistor")
      (fields
        (field (name "MANUFACTURER") "Generic Components")
        (field (name "PUBLISHER") "Altium Hobart Technology Centre")
      )
      (libsource (lib "RAL") (part "Res-SMD"))
    )
    (comp (ref "R42")
      (value "5.1K")
      (footprint "RES-SMD-0603 EX")
      (description "Resistor")
      (fields
        (field (name "MANUFACTURER") "Generic Components")
        (field (name "PUBLISHER") "Altium Hobart Technology Centre")
      )
      (libsource (lib "RAL") (part "Res-SMD"))
    )
    (comp (ref "R43")
      (value "2M/1206")
      (footprint "RES-SMD-0603 EX")
      (description "Resistor")
      (fields
        (field (name "MANUFACTURER") "Generic Components")
        (field (name "PUBLISHER") "Altium Hobart Technology Centre")
      )
      (libsource (lib "RAL") (part "Res-SMD"))
    )
    (comp (ref "R44")
      (value "2M/1206")
      (footprint "RES-SMD-0603 EX")
      (description "Resistor")
      (fields
        (field (name "MANUFACTURER") "Generic Components")
        (field (name "PUBLISHER") "Altium Hobart Technology Centre")
      )
      (libsource (lib "RAL") (part "Res-SMD"))
    )
    (comp (ref "R45")
      (value "2M/1206")
      (footprint "RES-SMD-0603 EX")
      (description "Resistor")
      (fields
        (field (name "MANUFACTURER") "Generic Components")
        (field (name "PUBLISHER") "Altium Hobart Technology Centre")
      )
      (libsource (lib "RAL") (part "Res-SMD"))
    )
    (comp (ref "R46")
      (value "2M/1206")
      (footprint "RES-SMD-0603 EX")
      (description "Resistor")
      (fields
        (field (name "MANUFACTURER") "Generic Components")
        (field (name "PUBLISHER") "Altium Hobart Technology Centre")
      )
      (libsource (lib "RAL") (part "Res-SMD"))
    )
    (comp (ref "R47")
      (value "200K")
      (footprint "RES-SMD-0603 EX")
      (description "Resistor")
      (fields
        (field (name "MANUFACTURER") "Generic Components")
        (field (name "PUBLISHER") "Altium Hobart Technology Centre")
      )
      (libsource (lib "RAL") (part "Res-SMD"))
    )
    (comp (ref "R48")
      (value "499K")
      (footprint "RES-SMD-0603 EX")
      (description "Resistor")
      (fields
        (field (name "MANUFACTURER") "Generic Components")
        (field (name "PUBLISHER") "Altium Hobart Technology Centre")
      )
      (libsource (lib "RAL") (part "Res-SMD"))
    )
    (comp (ref "R49")
      (value "51K/2010")
      (footprint "RES-SMD-0603 EX")
      (description "Resistor")
      (fields
        (field (name "MANUFACTURER") "Generic Components")
        (field (name "PUBLISHER") "Altium Hobart Technology Centre")
      )
      (libsource (lib "RAL") (part "Res-SMD"))
    )
    (comp (ref "R50")
      (value "51K/2010")
      (footprint "RES-SMD-0603 EX")
      (description "Resistor")
      (fields
        (field (name "MANUFACTURER") "Generic Components")
        (field (name "PUBLISHER") "Altium Hobart Technology Centre")
      )
      (libsource (lib "RAL") (part "Res-SMD"))
    )
    (comp (ref "R51")
      (value "10R")
      (footprint "RES-SMD-0603 EX")
      (description "Resistor")
      (fields
        (field (name "MANUFACTURER") "Generic Components")
        (field (name "PUBLISHER") "Altium Hobart Technology Centre")
      )
      (libsource (lib "RAL") (part "Res-SMD"))
    )
    (comp (ref "R52")
      (value "2M")
      (footprint "RES-SMD-0603 EX")
      (description "Resistor")
      (fields
        (field (name "MANUFACTURER") "Generic Components")
        (field (name "PUBLISHER") "Altium Hobart Technology Centre")
      )
      (libsource (lib "RAL") (part "Res-SMD"))
    )
    (comp (ref "R53")
      (value "5.1K")
      (footprint "RES-SMD-0603 EX")
      (description "Resistor")
      (fields
        (field (name "MANUFACTURER") "Generic Components")
        (field (name "PUBLISHER") "Altium Hobart Technology Centre")
      )
      (libsource (lib "RAL") (part "Res-SMD"))
    )
    (comp (ref "R54")
      (value "200K")
      (footprint "RES-SMD-0603 EX")
      (description "Resistor")
      (fields
        (field (name "MANUFACTURER") "Generic Components")
        (field (name "PUBLISHER") "Altium Hobart Technology Centre")
      )
      (libsource (lib "RAL") (part "Res-SMD"))
    )
    (comp (ref "R55")
      (value "499K")
      (footprint "RES-SMD-0603 EX")
      (description "Resistor")
      (fields
        (field (name "MANUFACTURER") "Generic Components")
        (field (name "PUBLISHER") "Altium Hobart Technology Centre")
      )
      (libsource (lib "RAL") (part "Res-SMD"))
    )
    (comp (ref "R56")
      (value "2M")
      (footprint "RES-SMD-0603 EX")
      (description "Resistor")
      (fields
        (field (name "MANUFACTURER") "Generic Components")
        (field (name "PUBLISHER") "Altium Hobart Technology Centre")
      )
      (libsource (lib "RAL") (part "Res-SMD"))
    )
    (comp (ref "R57")
      (value "200K")
      (footprint "RES-SMD-0603 EX")
      (description "Resistor")
      (fields
        (field (name "MANUFACTURER") "Generic Components")
        (field (name "PUBLISHER") "Altium Hobart Technology Centre")
      )
      (libsource (lib "RAL") (part "Res-SMD"))
    )
    (comp (ref "R58")
      (value "499K")
      (footprint "RES-SMD-0603 EX")
      (description "Resistor")
      (fields
        (field (name "MANUFACTURER") "Generic Components")
        (field (name "PUBLISHER") "Altium Hobart Technology Centre")
      )
      (libsource (lib "RAL") (part "Res-SMD"))
    )
    (comp (ref "R59")
      (value "2M")
      (footprint "RES-SMD-0603 EX")
      (description "Resistor")
      (fields
        (field (name "MANUFACTURER") "Generic Components")
        (field (name "PUBLISHER") "Altium Hobart Technology Centre")
      )
      (libsource (lib "RAL") (part "Res-SMD"))
    )
    (comp (ref "R60")
      (value "200K")
      (footprint "RES-SMD-0603 EX")
      (description "Resistor")
      (fields
        (field (name "MANUFACTURER") "Generic Components")
        (field (name "PUBLISHER") "Altium Hobart Technology Centre")
      )
      (libsource (lib "RAL") (part "Res-SMD"))
    )
    (comp (ref "R61")
      (value "30R/2010")
      (footprint "RES-SMD-0603 EX")
      (description "Resistor")
      (fields
        (field (name "MANUFACTURER") "Generic Components")
        (field (name "PUBLISHER") "Altium Hobart Technology Centre")
      )
      (libsource (lib "RAL") (part "Res-SMD"))
    )
    (comp (ref "R62")
      (value "30R/2010")
      (footprint "RES-SMD-0603 EX")
      (description "Resistor")
      (fields
        (field (name "MANUFACTURER") "Generic Components")
        (field (name "PUBLISHER") "Altium Hobart Technology Centre")
      )
      (libsource (lib "RAL") (part "Res-SMD"))
    )
    (comp (ref "R63")
      (value "0R")
      (footprint "RES-SMD-0603 EX")
      (description "Resistor")
      (fields
        (field (name "MANUFACTURER") "Generic Components")
        (field (name "PUBLISHER") "Altium Hobart Technology Centre")
      )
      (libsource (lib "RAL") (part "Res-SMD"))
    )
    (comp (ref "R64")
      (value "10K")
      (footprint "RES-SMD-0603 EX")
      (description "Resistor")
      (fields
        (field (name "MANUFACTURER") "Generic Components")
        (field (name "PUBLISHER") "Altium Hobart Technology Centre")
      )
      (libsource (lib "RAL") (part "Res-SMD"))
    )
    (comp (ref "R65")
      (value "10K/2010")
      (footprint "RES-SMD-0603 EX")
      (description "Resistor")
      (fields
        (field (name "MANUFACTURER") "Generic Components")
        (field (name "PUBLISHER") "Altium Hobart Technology Centre")
      )
      (libsource (lib "RAL") (part "Res-SMD"))
    )
    (comp (ref "R66")
      (value "2K/1206")
      (footprint "RES-SMD-0603 EX")
      (description "Resistor")
      (fields
        (field (name "MANUFACTURER") "Generic Components")
        (field (name "PUBLISHER") "Altium Hobart Technology Centre")
      )
      (libsource (lib "RAL") (part "Res-SMD"))
    )
    (comp (ref "R67")
      (value "10K/2010")
      (footprint "RES-SMD-0603 EX")
      (description "Resistor")
      (fields
        (field (name "MANUFACTURER") "Generic Components")
        (field (name "PUBLISHER") "Altium Hobart Technology Centre")
      )
      (libsource (lib "RAL") (part "Res-SMD"))
    )
    (comp (ref "R68")
      (value "499K")
      (footprint "RES-SMD-0603 EX")
      (description "Resistor")
      (fields
        (field (name "MANUFACTURER") "Generic Components")
        (field (name "PUBLISHER") "Altium Hobart Technology Centre")
      )
      (libsource (lib "RAL") (part "Res-SMD"))
    )
    (comp (ref "R69")
      (value "10K")
      (footprint "RES-SMD-0603 EX")
      (description "Resistor")
      (fields
        (field (name "MANUFACTURER") "Generic Components")
        (field (name "PUBLISHER") "Altium Hobart Technology Centre")
      )
      (libsource (lib "RAL") (part "Res-SMD"))
    )
    (comp (ref "R70")
      (value "10K/2010")
      (footprint "RES-SMD-0603 EX")
      (description "Resistor")
      (fields
        (field (name "MANUFACTURER") "Generic Components")
        (field (name "PUBLISHER") "Altium Hobart Technology Centre")
      )
      (libsource (lib "RAL") (part "Res-SMD"))
    )
    (comp (ref "R71")
      (value "10K/2010")
      (footprint "RES-SMD-0603 EX")
      (description "Resistor")
      (fields
        (field (name "MANUFACTURER") "Generic Components")
        (field (name "PUBLISHER") "Altium Hobart Technology Centre")
      )
      (libsource (lib "RAL") (part "Res-SMD"))
    )
    (comp (ref "R72")
      (value "10K/2010")
      (footprint "RES-SMD-0603 EX")
      (description "Resistor")
      (fields
        (field (name "MANUFACTURER") "Generic Components")
        (field (name "PUBLISHER") "Altium Hobart Technology Centre")
      )
      (libsource (lib "RAL") (part "Res-SMD"))
    )
    (comp (ref "R73")
      (value "10K/2010")
      (footprint "RES-SMD-0603 EX")
      (description "Resistor")
      (fields
        (field (name "MANUFACTURER") "Generic Components")
        (field (name "PUBLISHER") "Altium Hobart Technology Centre")
      )
      (libsource (lib "RAL") (part "Res-SMD"))
    )
    (comp (ref "R74")
      (value "10K/2010")
      (footprint "RES-SMD-0603 EX")
      (description "Resistor")
      (fields
        (field (name "MANUFACTURER") "Generic Components")
        (field (name "PUBLISHER") "Altium Hobart Technology Centre")
      )
      (libsource (lib "RAL") (part "Res-SMD"))
    )
    (comp (ref "R75")
      (value "10K/2010")
      (footprint "RES-SMD-0603 EX")
      (description "Resistor")
      (fields
        (field (name "MANUFACTURER") "Generic Components")
        (field (name "PUBLISHER") "Altium Hobart Technology Centre")
      )
      (libsource (lib "RAL") (part "Res-SMD"))
    )
    (comp (ref "R76")
      (value "5.1K/1206")
      (footprint "RES-SMD-0603 EX")
      (description "Resistor")
      (fields
        (field (name "MANUFACTURER") "Generic Components")
        (field (name "PUBLISHER") "Altium Hobart Technology Centre")
      )
      (libsource (lib "RAL") (part "Res-SMD"))
    )
    (comp (ref "R77")
      (value "5.1K")
      (footprint "RES-SMD-0603 EX")
      (description "Resistor")
      (fields
        (field (name "MANUFACTURER") "Generic Components")
        (field (name "PUBLISHER") "Altium Hobart Technology Centre")
      )
      (libsource (lib "RAL") (part "Res-SMD"))
    )
    (comp (ref "R78")
      (value "2M")
      (footprint "RES-SMD-0603 EX")
      (description "Resistor")
      (fields
        (field (name "MANUFACTURER") "Generic Components")
        (field (name "PUBLISHER") "Altium Hobart Technology Centre")
      )
      (libsource (lib "RAL") (part "Res-SMD"))
    )
    (comp (ref "R79")
      (value "10K/2010")
      (footprint "RES-SMD-0603 EX")
      (description "Resistor")
      (fields
        (field (name "MANUFACTURER") "Generic Components")
        (field (name "PUBLISHER") "Altium Hobart Technology Centre")
      )
      (libsource (lib "RAL") (part "Res-SMD"))
    )
    (comp (ref "R80")
      (value "10R/0805")
      (footprint "RES-SMD-0603 EX")
      (description "Resistor")
      (fields
        (field (name "MANUFACTURER") "Generic Components")
        (field (name "PUBLISHER") "Altium Hobart Technology Centre")
      )
      (libsource (lib "RAL") (part "Res-SMD"))
    )
    (comp (ref "R81")
      (value "2M")
      (footprint "RES-SMD-0603 EX")
      (description "Resistor")
      (fields
        (field (name "MANUFACTURER") "Generic Components")
        (field (name "PUBLISHER") "Altium Hobart Technology Centre")
      )
      (libsource (lib "RAL") (part "Res-SMD"))
    )
    (comp (ref "R82")
      (value "0R")
      (footprint "RES-SMD-0603 EX")
      (description "Resistor")
      (fields
        (field (name "MANUFACTURER") "Generic Components")
        (field (name "PUBLISHER") "Altium Hobart Technology Centre")
      )
      (libsource (lib "RAL") (part "Res-SMD"))
    )
    (comp (ref "R83")
      (value "30K")
      (footprint "RES-SMD-0603 EX")
      (description "Resistor")
      (fields
        (field (name "MANUFACTURER") "Generic Components")
        (field (name "PUBLISHER") "Altium Hobart Technology Centre")
      )
      (libsource (lib "RAL") (part "Res-SMD"))
    )
    (comp (ref "R84")
      (value "10R")
      (footprint "RES-SMD-0603 EX")
      (description "Resistor")
      (fields
        (field (name "MANUFACTURER") "Generic Components")
        (field (name "PUBLISHER") "Altium Hobart Technology Centre")
      )
      (libsource (lib "RAL") (part "Res-SMD"))
    )
    (comp (ref "R85")
      (value "10K/0805")
      (footprint "RES-SMD-0603 EX")
      (description "Resistor")
      (fields
        (field (name "MANUFACTURER") "Generic Components")
        (field (name "PUBLISHER") "Altium Hobart Technology Centre")
      )
      (libsource (lib "RAL") (part "Res-SMD"))
    )
    (comp (ref "R86")
      (value "2M")
      (footprint "RES-SMD-0603 EX")
      (description "Resistor")
      (fields
        (field (name "MANUFACTURER") "Generic Components")
        (field (name "PUBLISHER") "Altium Hobart Technology Centre")
      )
      (libsource (lib "RAL") (part "Res-SMD"))
    )
    (comp (ref "R87")
      (value "5.1K/0805")
      (footprint "RES-SMD-0805 EX")
      (description "Resistor")
      (fields
        (field (name "MANUFACTURER") "Generic Components")
        (field (name "PUBLISHER") "Altium Hobart Technology Centre")
      )
      (libsource (lib "RAL") (part "Res-SMD"))
    )
    (comp (ref "R88")
      (value "1K")
      (footprint "RES-SMD-0603 EX")
      (description "Resistor")
      (fields
        (field (name "MANUFACTURER") "Generic Components")
        (field (name "PUBLISHER") "Altium Hobart Technology Centre")
      )
      (libsource (lib "RAL") (part "Res-SMD"))
    )
    (comp (ref "R89")
      (value "100R")
      (footprint "RES-SMD-0603 EX")
      (description "Resistor")
      (fields
        (field (name "MANUFACTURER") "Generic Components")
        (field (name "PUBLISHER") "Altium Hobart Technology Centre")
      )
      (libsource (lib "RAL") (part "Res-SMD"))
    )
    (comp (ref "R90")
      (value "150R/1206")
      (footprint "RES-SMD-0603 EX")
      (description "Resistor")
      (fields
        (field (name "MANUFACTURER") "Generic Components")
        (field (name "PUBLISHER") "Altium Hobart Technology Centre")
      )
      (libsource (lib "RAL") (part "Res-SMD"))
    )
    (comp (ref "R91")
      (value "150R/1206")
      (footprint "RES-SMD-0603 EX")
      (description "Resistor")
      (fields
        (field (name "MANUFACTURER") "Generic Components")
        (field (name "PUBLISHER") "Altium Hobart Technology Centre")
      )
      (libsource (lib "RAL") (part "Res-SMD"))
    )
    (comp (ref "R92")
      (value "10R/0805")
      (footprint "RES-SMD-0603 EX")
      (description "Resistor")
      (fields
        (field (name "MANUFACTURER") "Generic Components")
        (field (name "PUBLISHER") "Altium Hobart Technology Centre")
      )
      (libsource (lib "RAL") (part "Res-SMD"))
    )
    (comp (ref "R93")
      (value "0.33R/2010")
      (footprint "RES-SMD-0603 EX")
      (description "Resistor")
      (fields
        (field (name "MANUFACTURER") "Generic Components")
        (field (name "PUBLISHER") "Altium Hobart Technology Centre")
      )
      (libsource (lib "RAL") (part "Res-SMD"))
    )
    (comp (ref "R94")
      (value "0.33R/2010")
      (footprint "RES-SMD-0603 EX")
      (description "Resistor")
      (fields
        (field (name "MANUFACTURER") "Generic Components")
        (field (name "PUBLISHER") "Altium Hobart Technology Centre")
      )
      (libsource (lib "RAL") (part "Res-SMD"))
    )
    (comp (ref "R95")
      (value "0R")
      (footprint "RES-SMD-0603 EX")
      (description "Resistor")
      (fields
        (field (name "MANUFACTURER") "Generic Components")
        (field (name "PUBLISHER") "Altium Hobart Technology Centre")
      )
      (libsource (lib "RAL") (part "Res-SMD"))
    )
    (comp (ref "R96")
      (value "2K/1206")
      (footprint "RES-SMD-0603 EX")
      (description "Resistor")
      (fields
        (field (name "MANUFACTURER") "Generic Components")
        (field (name "PUBLISHER") "Altium Hobart Technology Centre")
      )
      (libsource (lib "RAL") (part "Res-SMD"))
    )
    (comp (ref "R97")
      (value "20K")
      (footprint "RES-SMD-0603 EX")
      (description "Resistor")
      (fields
        (field (name "MANUFACTURER") "Generic Components")
        (field (name "PUBLISHER") "Altium Hobart Technology Centre")
      )
      (libsource (lib "RAL") (part "Res-SMD"))
    )
    (comp (ref "R98")
      (value "300K")
      (footprint "RES-SMD-0603 EX")
      (description "Resistor")
      (fields
        (field (name "MANUFACTURER") "Generic Components")
        (field (name "PUBLISHER") "Altium Hobart Technology Centre")
      )
      (libsource (lib "RAL") (part "Res-SMD"))
    )
    (comp (ref "R99")
      (value "100K")
      (footprint "RES-SMD-0603 EX")
      (description "Resistor")
      (fields
        (field (name "MANUFACTURER") "Generic Components")
        (field (name "PUBLISHER") "Altium Hobart Technology Centre")
      )
      (libsource (lib "RAL") (part "Res-SMD"))
    )
    (comp (ref "R100")
      (value "15K")
      (footprint "RES-SMD-0603 EX")
      (description "Resistor")
      (fields
        (field (name "MANUFACTURER") "Generic Components")
        (field (name "PUBLISHER") "Altium Hobart Technology Centre")
      )
      (libsource (lib "RAL") (part "Res-SMD"))
    )
    (comp (ref "R101")
      (value "5.1K/1206")
      (footprint "RES-SMD-0603 EX")
      (description "Resistor")
      (fields
        (field (name "MANUFACTURER") "Generic Components")
        (field (name "PUBLISHER") "Altium Hobart Technology Centre")
      )
      (libsource (lib "RAL") (part "Res-SMD"))
    )
    (comp (ref "R102")
      (value "100R")
      (footprint "RES-SMD-0603 EX")
      (description "Resistor")
      (fields
        (field (name "MANUFACTURER") "Generic Components")
        (field (name "PUBLISHER") "Altium Hobart Technology Centre")
      )
      (libsource (lib "RAL") (part "Res-SMD"))
    )
    (comp (ref "R103")
      (value "10K")
      (footprint "RES-SMD-0603 EX")
      (description "Resistor")
      (fields
        (field (name "MANUFACTURER") "Generic Components")
        (field (name "PUBLISHER") "Altium Hobart Technology Centre")
      )
      (libsource (lib "RAL") (part "Res-SMD"))
    )
    (comp (ref "R104")
      (value "20k")
      (footprint "RES-SMD-0603 EX")
      (description "Resistor")
      (fields
        (field (name "MANUFACTURER") "Generic Components")
        (field (name "PUBLISHER") "Altium Hobart Technology Centre")
      )
      (libsource (lib "RAL") (part "Res-SMD"))
    )
    (comp (ref "R105")
      (value "5.1K")
      (footprint "RES-SMD-0603 EX")
      (description "Resistor")
      (fields
        (field (name "MANUFACTURER") "Generic Components")
        (field (name "PUBLISHER") "Altium Hobart Technology Centre")
      )
      (libsource (lib "RAL") (part "Res-SMD"))
    )
    (comp (ref "R106")
      (value "100R")
      (footprint "RES-SMD-0603 EX")
      (description "Resistor")
      (fields
        (field (name "MANUFACTURER") "Generic Components")
        (field (name "PUBLISHER") "Altium Hobart Technology Centre")
      )
      (libsource (lib "RAL") (part "Res-SMD"))
    )
    (comp (ref "R107")
      (value "510R")
      (footprint "RES-SMD-0603 EX")
      (description "Resistor")
      (fields
        (field (name "MANUFACTURER") "Generic Components")
        (field (name "PUBLISHER") "Altium Hobart Technology Centre")
      )
      (libsource (lib "RAL") (part "Res-SMD"))
    )
    (comp (ref "R108")
      (value "5.1K")
      (footprint "RES-SMD-0603 EX")
      (description "Resistor")
      (fields
        (field (name "MANUFACTURER") "Generic Components")
        (field (name "PUBLISHER") "Altium Hobart Technology Centre")
      )
      (libsource (lib "RAL") (part "Res-SMD"))
    )
    (comp (ref "R109")
      (value "10K")
      (footprint "RES-SMD-0603 EX")
      (description "Resistor")
      (fields
        (field (name "MANUFACTURER") "Generic Components")
        (field (name "PUBLISHER") "Altium Hobart Technology Centre")
      )
      (libsource (lib "RAL") (part "Res-SMD"))
    )
    (comp (ref "R110")
      (value "430R")
      (footprint "RES-SMD-0603 EX")
      (description "Resistor")
      (fields
        (field (name "MANUFACTURER") "Generic Components")
        (field (name "PUBLISHER") "Altium Hobart Technology Centre")
      )
      (libsource (lib "RAL") (part "Res-SMD"))
    )
    (comp (ref "R111")
      (value "22R")
      (footprint "RES-SMD-0603 EX")
      (description "Resistor")
      (fields
        (field (name "MANUFACTURER") "Generic Components")
        (field (name "PUBLISHER") "Altium Hobart Technology Centre")
      )
      (libsource (lib "RAL") (part "Res-SMD"))
    )
    (comp (ref "R112")
      (value "4.3K")
      (footprint "RES-SMD-0603 EX")
      (description "Resistor")
      (fields
        (field (name "MANUFACTURER") "Generic Components")
        (field (name "PUBLISHER") "Altium Hobart Technology Centre")
      )
      (libsource (lib "RAL") (part "Res-SMD"))
    )
    (comp (ref "R113")
      (value "1K")
      (footprint "RES-SMD-0603 EX")
      (description "Resistor")
      (fields
        (field (name "MANUFACTURER") "Generic Components")
        (field (name "PUBLISHER") "Altium Hobart Technology Centre")
      )
      (libsource (lib "RAL") (part "Res-SMD"))
    )
    (comp (ref "R114")
      (value "10R/0805")
      (footprint "RES-SMD-0603 EX")
      (description "Resistor")
      (fields
        (field (name "MANUFACTURER") "Generic Components")
        (field (name "PUBLISHER") "Altium Hobart Technology Centre")
      )
      (libsource (lib "RAL") (part "Res-SMD"))
    )
    (comp (ref "R115")
      (value "510R")
      (footprint "RES-SMD-0603 EX")
      (description "Resistor")
      (fields
        (field (name "MANUFACTURER") "Generic Components")
        (field (name "PUBLISHER") "Altium Hobart Technology Centre")
      )
      (libsource (lib "RAL") (part "Res-SMD"))
    )
    (comp (ref "R116")
      (value "5.1K")
      (footprint "RES-SMD-0603 EX")
      (description "Resistor")
      (fields
        (field (name "MANUFACTURER") "Generic Components")
        (field (name "PUBLISHER") "Altium Hobart Technology Centre")
      )
      (libsource (lib "RAL") (part "Res-SMD"))
    )
    (comp (ref "R117")
      (value "1K")
      (footprint "RES-SMD-0603 EX")
      (description "Resistor")
      (fields
        (field (name "MANUFACTURER") "Generic Components")
        (field (name "PUBLISHER") "Altium Hobart Technology Centre")
      )
      (libsource (lib "RAL") (part "Res-SMD"))
    )
    (comp (ref "R118")
      (value "100K")
      (footprint "RES-SMD-0603 EX")
      (description "Resistor")
      (fields
        (field (name "MANUFACTURER") "Generic Components")
        (field (name "PUBLISHER") "Altium Hobart Technology Centre")
      )
      (libsource (lib "RAL") (part "Res-SMD"))
    )
    (comp (ref "R119")
      (value "0.33R/2010")
      (footprint "RES-SMD-0603 EX")
      (description "Resistor")
      (fields
        (field (name "MANUFACTURER") "Generic Components")
        (field (name "PUBLISHER") "Altium Hobart Technology Centre")
      )
      (libsource (lib "RAL") (part "Res-SMD"))
    )
    (comp (ref "R120")
      (value "0.33R/2010")
      (footprint "RES-SMD-0603 EX")
      (description "Resistor")
      (fields
        (field (name "MANUFACTURER") "Generic Components")
        (field (name "PUBLISHER") "Altium Hobart Technology Centre")
      )
      (libsource (lib "RAL") (part "Res-SMD"))
    )
    (comp (ref "R121")
      (value "0.33R/2010")
      (footprint "RES-SMD-0603 EX")
      (description "Resistor")
      (fields
        (field (name "MANUFACTURER") "Generic Components")
        (field (name "PUBLISHER") "Altium Hobart Technology Centre")
      )
      (libsource (lib "RAL") (part "Res-SMD"))
    )
    (comp (ref "R122")
      (value "0.33R/2010")
      (footprint "RES-SMD-0603 EX")
      (description "Resistor")
      (fields
        (field (name "MANUFACTURER") "Generic Components")
        (field (name "PUBLISHER") "Altium Hobart Technology Centre")
      )
      (libsource (lib "RAL") (part "Res-SMD"))
    )
    (comp (ref "R123")
      (value "10K/0805")
      (footprint "RES-SMD-0603 EX")
      (description "Resistor")
      (fields
        (field (name "MANUFACTURER") "Generic Components")
        (field (name "PUBLISHER") "Altium Hobart Technology Centre")
      )
      (libsource (lib "RAL") (part "Res-SMD"))
    )
    (comp (ref "R124")
      (value "1.3K")
      (footprint "RES-SMD-0603 EX")
      (description "Resistor")
      (fields
        (field (name "MANUFACTURER") "Generic Components")
        (field (name "PUBLISHER") "Altium Hobart Technology Centre")
      )
      (libsource (lib "RAL") (part "Res-SMD"))
    )
    (comp (ref "R125")
      (value "4.3K")
      (footprint "RES-SMD-0603 EX")
      (description "Resistor")
      (fields
        (field (name "MANUFACTURER") "Generic Components")
        (field (name "PUBLISHER") "Altium Hobart Technology Centre")
      )
      (libsource (lib "RAL") (part "Res-SMD"))
    )
    (comp (ref "R126")
      (value "5.1K")
      (footprint "RES-SMD-0603 EX")
      (description "Resistor")
      (fields
        (field (name "MANUFACTURER") "Generic Components")
        (field (name "PUBLISHER") "Altium Hobart Technology Centre")
      )
      (libsource (lib "RAL") (part "Res-SMD"))
    )
    (comp (ref "R127")
      (value "10K")
      (footprint "RES-SMD-0603 EX")
      (description "Resistor")
      (fields
        (field (name "MANUFACTURER") "Generic Components")
        (field (name "PUBLISHER") "Altium Hobart Technology Centre")
      )
      (libsource (lib "RAL") (part "Res-SMD"))
    )
    (comp (ref "R128")
      (value "30K")
      (footprint "RES-SMD-0603 EX")
      (description "Resistor")
      (fields
        (field (name "MANUFACTURER") "Generic Components")
        (field (name "PUBLISHER") "Altium Hobart Technology Centre")
      )
      (libsource (lib "RAL") (part "Res-SMD"))
    )
    (comp (ref "R129")
      (value "1K")
      (footprint "RES-SMD-0603 EX")
      (description "Resistor")
      (fields
        (field (name "MANUFACTURER") "Generic Components")
        (field (name "PUBLISHER") "Altium Hobart Technology Centre")
      )
      (libsource (lib "RAL") (part "Res-SMD"))
    )
    (comp (ref "R130")
      (value "100K")
      (footprint "RES-SMD-0603 EX")
      (description "Resistor")
      (fields
        (field (name "MANUFACTURER") "Generic Components")
        (field (name "PUBLISHER") "Altium Hobart Technology Centre")
      )
      (libsource (lib "RAL") (part "Res-SMD"))
    )
    (comp (ref "R131")
      (value "100K/2010")
      (footprint "RES-SMD-0603 EX")
      (description "Resistor")
      (fields
        (field (name "MANUFACTURER") "Generic Components")
        (field (name "PUBLISHER") "Altium Hobart Technology Centre")
      )
      (libsource (lib "RAL") (part "Res-SMD"))
    )
    (comp (ref "R132")
      (value "499K/1206")
      (footprint "RES-SMD-0603 EX")
      (description "Resistor")
      (fields
        (field (name "MANUFACTURER") "Generic Components")
        (field (name "PUBLISHER") "Altium Hobart Technology Centre")
      )
      (libsource (lib "RAL") (part "Res-SMD"))
    )
    (comp (ref "R133")
      (value "499K/1206")
      (footprint "RES-SMD-0603 EX")
      (description "Resistor")
      (fields
        (field (name "MANUFACTURER") "Generic Components")
        (field (name "PUBLISHER") "Altium Hobart Technology Centre")
      )
      (libsource (lib "RAL") (part "Res-SMD"))
    )
    (comp (ref "R134")
      (value "499K/1206")
      (footprint "RES-SMD-0603 EX")
      (description "Resistor")
      (fields
        (field (name "MANUFACTURER") "Generic Components")
        (field (name "PUBLISHER") "Altium Hobart Technology Centre")
      )
      (libsource (lib "RAL") (part "Res-SMD"))
    )
    (comp (ref "R135")
      (value "499K/1206")
      (footprint "RES-SMD-0603 EX")
      (description "Resistor")
      (fields
        (field (name "MANUFACTURER") "Generic Components")
        (field (name "PUBLISHER") "Altium Hobart Technology Centre")
      )
      (libsource (lib "RAL") (part "Res-SMD"))
    )
    (comp (ref "R136")
      (value "100K")
      (footprint "RES-SMD-0603 EX")
      (description "Resistor")
      (fields
        (field (name "MANUFACTURER") "Generic Components")
        (field (name "PUBLISHER") "Altium Hobart Technology Centre")
      )
      (libsource (lib "RAL") (part "Res-SMD"))
    )
    (comp (ref "R137")
      (value "100K/2010")
      (footprint "RES-SMD-0603 EX")
      (description "Resistor")
      (fields
        (field (name "MANUFACTURER") "Generic Components")
        (field (name "PUBLISHER") "Altium Hobart Technology Centre")
      )
      (libsource (lib "RAL") (part "Res-SMD"))
    )
    (comp (ref "R138")
      (value "100K/2010")
      (footprint "RES-SMD-0603 EX")
      (description "Resistor")
      (fields
        (field (name "MANUFACTURER") "Generic Components")
        (field (name "PUBLISHER") "Altium Hobart Technology Centre")
      )
      (libsource (lib "RAL") (part "Res-SMD"))
    )
    (comp (ref "R139")
      (value "499K/1206")
      (footprint "RES-SMD-0603 EX")
      (description "Resistor")
      (fields
        (field (name "MANUFACTURER") "Generic Components")
        (field (name "PUBLISHER") "Altium Hobart Technology Centre")
      )
      (libsource (lib "RAL") (part "Res-SMD"))
    )
    (comp (ref "R140")
      (value "499K/1206")
      (footprint "RES-SMD-0603 EX")
      (description "Resistor")
      (fields
        (field (name "MANUFACTURER") "Generic Components")
        (field (name "PUBLISHER") "Altium Hobart Technology Centre")
      )
      (libsource (lib "RAL") (part "Res-SMD"))
    )
    (comp (ref "R141")
      (value "499K/1206")
      (footprint "RES-SMD-0603 EX")
      (description "Resistor")
      (fields
        (field (name "MANUFACTURER") "Generic Components")
        (field (name "PUBLISHER") "Altium Hobart Technology Centre")
      )
      (libsource (lib "RAL") (part "Res-SMD"))
    )
    (comp (ref "R142")
      (value "499K/1206")
      (footprint "RES-SMD-0603 EX")
      (description "Resistor")
      (fields
        (field (name "MANUFACTURER") "Generic Components")
        (field (name "PUBLISHER") "Altium Hobart Technology Centre")
      )
      (libsource (lib "RAL") (part "Res-SMD"))
    )
    (comp (ref "R143")
      (value "~")
      (footprint "RES-SMD-0603 EX")
      (description "No connect")
      (fields
        (field (name "MANUFACTURER") "Generic Components")
        (field (name "PUBLISHER") "Altium Hobart Technology Centre")
      )
      (libsource (lib "RAL") (part "Res-SMD"))
    )
    (comp (ref "R144")
      (value "100K/2010")
      (footprint "RES-SMD-0603 EX")
      (description "Resistor")
      (fields
        (field (name "MANUFACTURER") "Generic Components")
        (field (name "PUBLISHER") "Altium Hobart Technology Centre")
      )
      (libsource (lib "RAL") (part "Res-SMD"))
    )
    (comp (ref "R145")
      (value "100K")
      (footprint "RES-SMD-0603 EX")
      (description "Resistor")
      (fields
        (field (name "MANUFACTURER") "Generic Components")
        (field (name "PUBLISHER") "Altium Hobart Technology Centre")
      )
      (libsource (lib "RAL") (part "Res-SMD"))
    )
    (comp (ref "R146")
      (value "~")
      (footprint "RES-SMD-0603 EX")
      (description "No connect")
      (fields
        (field (name "MANUFACTURER") "Generic Components")
        (field (name "PUBLISHER") "Altium Hobart Technology Centre")
      )
      (libsource (lib "RAL") (part "Res-SMD"))
    )
    (comp (ref "R147")
      (value "~")
      (footprint "RES-SMD-0603 EX")
      (description "No connect")
      (fields
        (field (name "MANUFACTURER") "Generic Components")
        (field (name "PUBLISHER") "Altium Hobart Technology Centre")
      )
      (libsource (lib "RAL") (part "Res-SMD"))
    )
    (comp (ref "RV1")
      (value "S20K420")
      (footprint "VAR_B72220S0301K101")
      (description "Varistor 420VAC 8000A(8/20us) B72220S0421K101")
      (fields (field (name "MP") "B72220S0301K101") (field (name "MF") "TDK"))
      (libsource (lib "Lib_RD_Cg") (part "Varistor B772"))
    )
    (comp (ref "RV2")
      (value "S20K420")
      (footprint "VAR_B72220S0301K101")
      (description "Varistor 420VAC 8000A(8/20us) B72220S0421K101")
      (fields (field (name "MP") "B72220S0301K101") (field (name "MF") "TDK"))
      (libsource (lib "Lib_RD_Cg") (part "Varistor B772"))
    )
    (comp (ref "RV3")
      (value "S20K420")
      (footprint "VAR_B72220S0301K101")
      (description "Varistor 420VAC 8000A(8/20us) B72220S0421K101")
      (fields (field (name "MP") "B72220S0301K101") (field (name "MF") "TDK"))
      (libsource (lib "Lib_RD_Cg") (part "Varistor B772"))
    )
    (comp (ref "RV4")
      (value "S20K420")
      (footprint "VAR_B72220S0301K101")
      (description "Varistor 420VAC 8000A(8/20us) B72220S0421K101")
      (fields (field (name "MP") "B72220S0301K101") (field (name "MF") "TDK"))
      (libsource (lib "Lib_RD_Cg") (part "Varistor B772"))
    )
    (comp (ref "T1")
      (value "~")
      (footprint "EE16/7/4 (E16)")
      (description "Off-Line Transformer WE-UNIT , L=0.9mH")
      (fields
        (field (name "PARTNO") "749118205")
        (field (name "MANUFACTURER") "Würth Elektronik eiSos GmbH")
        (field (name "CREATED BY") "Otto Christin")
      )
      (libsource (lib "RAL") (part "Tranf6"))
    )
    (comp (ref "T2")
      (value "BAX")
      (footprint "BAX_DVD3")
      (description "Bien ap xung DVD")
      (fields (field (name "DESIGNED BY") "VanDungEvn"))
      (libsource (lib "Lib_RD_Cg") (part "Tranfomer 2-4"))
    )
    (comp (ref "U1")
      (value "ULN2003A")
      (footprint "TSSOP-16-TI")
      (description "Power Switch/Driver 1:1 Darlington 500mA 16-SOP")
      (fields (field (name "MF") "UMW"))
      (libsource (lib "Lib_RD_Cg") (part "ULN2003A"))
    )
    (comp (ref "U2")
      (value "DC STK-PL")
      (footprint "Bien ap do Current")
      (description "Bien dong sinomags STK-PL 50 0LSB8 \r\nSTK-PL/P1")
      (fields (field (name "DESIGNED BY") "VanDungEvn"))
      (libsource (lib "Lib_RD_Cg") (part "Current sensor"))
    )
    (comp (ref "U3")
      (value "L1117 50C")
      (footprint "SOT89N (3D)")
      (description "IC 5V thay the 78M05")
      (fields (field (name "PUBLISHER") "Altium Limited"))
      (libsource (lib "Lib_RD_Cg") (part "AZ1117CR-3.3"))
    )
    (comp (ref "U4")
      (value "MC7912BD2T")
      (footprint "HDR1x3 BIG")
      (description "IC -12V")
      (fields (field (name "PUBLISHER") "Altium Limited"))
      (libsource (lib "Lib_RD_Cg") (part "7133_1"))
    )
    (comp (ref "U5")
      (value "ICE3AR0680jz")
      (footprint "SOIC127P600X175-8N")
      (description "HIGH PERFORMANCE CURRENT MODE PWM CONTROLLER")
      (fields (field (name "MP") "UC2845BD1"))
      (libsource (lib "Lib_RD_Cg") (part "ICE3AR0680jz"))
    )
    (comp (ref "U6")
      (value "UC2845A")
      (footprint "SOIC127P600X175-8N")
      (fields (field (name "MF") "ON Semiconductor") (field (name "MP") "UC3843BVD1G"))
      (libsource (lib "Lib_RD_Cg") (part "UC3843BVD1G"))
    )
    (comp (ref "U7")
      (value "TL084")
      (footprint "DIP794W45P254L959H508Q8")
      (description "Dual, 32-V, 1-MHz op amp")
      (fields (field (name "MP") "LM358N/NOPB") (field (name "MF") "Texas Instruments"))
      (libsource (lib "Lib_RD_Cg") (part "LM358N/NOPB"))
    )
    (comp (ref "U8")
      (value "617A-3")
      (footprint "OPTO TRANSISTOR_SOP-4")
      (description "OPTOISOLATOR 3.75KV TRANS 4-SOP")
      (fields (field (name "MPN") "VOM617A-2T"))
      (libsource (lib "BYTECH_HW_LIB_2019 (1)") (part "VOM617A-2T"))
    )
    (comp (ref "U9")
      (value "TL431BV")
      (footprint "TL431")
      (description "SOIC 8 TL431BD")
      (libsource (lib "Lib_RD_Cg") (part "TL431"))
    )
    (comp (ref "U10")
      (value "DC STK-PL")
      (footprint "Bien ap do Current")
      (description "Bien dong sinomags STK-PL 50 0LSB8 \r\nSTK-PL/P1")
      (fields (field (name "DESIGNED BY") "VanDungEvn"))
      (libsource (lib "Lib_RD_Cg") (part "Current sensor"))
    )
    (comp (ref "V1") (value "~") (libsource (lib "Lib_RD_Cg") (part "D882M")))
    (comp (ref "V2") (value "~") (libsource (lib "Lib_RD_Cg") (part "D882M")))
  )
  (nets
    (net (code "1") (name "+5V") (class "Default")
      (node (ref "C3") (pin "2") (pinfunction "2_2") (pintype "passive"))
      (node (ref "C40") (pin "1") (pinfunction "1_1") (pintype "passive"))
      (node (ref "C41") (pin "1") (pinfunction "1_1") (pintype "passive"))
      (node (ref "C67") (pin "2") (pinfunction "2_2") (pintype "passive"))
      (node (ref "C85") (pin "1") (pinfunction "1_1") (pintype "passive"))
      (node (ref "J5") (pin "15") (pinfunction "15_15") (pintype "passive"))
      (node (ref "J5") (pin "16") (pinfunction "16_16") (pintype "passive"))
      (node (ref "R101") (pin "2") (pinfunction "2_2") (pintype "passive"))
      (node (ref "R66") (pin "2") (pinfunction "2_2") (pintype "passive"))
      (node (ref "R76") (pin "2") (pinfunction "2_2") (pintype "passive"))
      (node (ref "R77") (pin "2") (pinfunction "2_2") (pintype "passive"))
      (node (ref "R96") (pin "2") (pinfunction "2_2") (pintype "passive"))
      (node (ref "U10") (pin "14") (pinfunction "Vcc_14") (pintype "passive"))
      (node (ref "U2") (pin "13") (pinfunction "Gnd_13") (pintype "passive"))
      (node (ref "U2") (pin "14") (pinfunction "Vcc_14") (pintype "passive"))
      (node (ref "U3") (pin "2") (pinfunction "OUT_2") (pintype "power_in"))
    )
    (net (code "2") (name "+10V") (class "Default")
      (node (ref "C42") (pin "1") (pinfunction "1_1") (pintype "passive"))
      (node (ref "C43") (pin "1") (pinfunction "1_1") (pintype "passive"))
      (node (ref "C44") (pin "1") (pinfunction "1_1") (pintype "passive"))
      (node (ref "C45") (pin "1") (pinfunction "1_1") (pintype "passive"))
      (node (ref "C46") (pin "1") (pinfunction "1_1") (pintype "passive"))
      (node (ref "C47") (pin "1") (pinfunction "1_1") (pintype "passive"))
      (node (ref "C48") (pin "1") (pinfunction "1_1") (pintype "passive"))
      (node (ref "D1") (pin "1") (pinfunction "A_1") (pintype "passive"))
      (node (ref "D15") (pin "3") (pinfunction "K_3") (pintype "passive"))
      (node (ref "D4") (pin "3") (pinfunction "K_3") (pintype "passive"))
      (node (ref "R106") (pin "1") (pinfunction "1_1") (pintype "passive"))
      (node (ref "R113") (pin "1") (pinfunction "1_1") (pintype "passive"))
      (node (ref "R79") (pin "1") (pinfunction "1_1") (pintype "passive"))
      (node (ref "R8") (pin "1") (pinfunction "1_1") (pintype "passive"))
      (node (ref "R97") (pin "1") (pinfunction "1_1") (pintype "passive"))
      (node (ref "U3") (pin "3") (pinfunction "IN_3") (pintype "power_in"))
    )
    (net (code "3") (name "+12V") (class "Default")
      (node (ref "C18") (pin "1") (pinfunction "1_1") (pintype "passive"))
      (node (ref "C62") (pin "2") (pinfunction "2_2") (pintype "passive"))
      (node (ref "C63") (pin "2") (pinfunction "2_2") (pintype "passive"))
      (node (ref "C64") (pin "1") (pinfunction "1_1") (pintype "passive"))
      (node (ref "C65") (pin "1") (pinfunction "1_1") (pintype "passive"))
      (node (ref "C73") (pin "1") (pinfunction "1_1") (pintype "passive"))
      (node (ref "D23") (pin "3") (pinfunction "K_3") (pintype "passive"))
      (node (ref "H1") (pin "4") (pinfunction "4_4") (pintype "passive"))
      (node (ref "H2") (pin "4") (pinfunction "4_4") (pintype "passive"))
      (node (ref "J1") (pin "2") (pinfunction "2_2") (pintype "passive"))
      (node (ref "J5") (pin "17") (pinfunction "17_17") (pintype "passive"))
      (node (ref "K5") (pin "3") (pinfunction "3_3") (pintype "passive"))
      (node (ref "L1") (pin "1") (pinfunction "1_1") (pintype "passive"))
      (node (ref "R91") (pin "1") (pinfunction "1_1") (pintype "passive"))
      (node (ref "R99") (pin "2") (pinfunction "2_2") (pintype "passive"))
      (node (ref "U7") (pin "8") (pinfunction "V+_8") (pintype "power_in"))
    )
    (net (code "4") (name "-12V") (class "Default")
      (node (ref "C55") (pin "2") (pinfunction "2_2") (pintype "passive"))
      (node (ref "C82") (pin "1") (pinfunction "1_1") (pintype "passive"))
      (node (ref "J5") (pin "13") (pinfunction "13_13") (pintype "passive"))
      (node (ref "U4") (pin "3") (pinfunction "OUT_3") (pintype "power_in"))
      (node (ref "U7") (pin "4") (pinfunction "GND_4") (pintype "power_in"))
    )
    (net (code "5") (name "/CTR_Relay") (class "Default")
      (node (ref "J5") (pin "18") (pinfunction "18_18") (pintype "passive"))
      (node (ref "R4") (pin "1") (pinfunction "1_1") (pintype "passive"))
    )
    (net (code "6") (name "/Ctr_Fan1") (class "Default")
      (node (ref "J5") (pin "22") (pinfunction "22_22") (pintype "passive"))
      (node (ref "R80") (pin "1") (pinfunction "1_1") (pintype "passive"))
      (node (ref "R85") (pin "1") (pinfunction "1_1") (pintype "passive"))
      (node (ref "R92") (pin "1") (pinfunction "1_1") (pintype "passive"))
    )
    (net (code "7") (name "/Ctr_Fan2") (class "Default")
      (node (ref "J5") (pin "24") (pinfunction "24_24") (pintype "passive"))
      (node (ref "R114") (pin "1") (pinfunction "1_1") (pintype "passive"))
      (node (ref "R123") (pin "1") (pinfunction "1_1") (pintype "passive"))
      (node (ref "R92") (pin "2") (pinfunction "2_2") (pintype "passive"))
    )
    (net (code "8") (name "/EVN_L") (class "Default")
      (node (ref "J5") (pin "7") (pinfunction "7_7") (pintype "passive"))
      (node (ref "R16") (pin "2") (pinfunction "2_2") (pintype "passive"))
    )
    (net (code "9") (name "/EVN_N") (class "Default")
      (node (ref "J5") (pin "8") (pinfunction "8_8") (pintype "passive"))
      (node (ref "R46") (pin "2") (pinfunction "2_2") (pintype "passive"))
    )
    (net (code "10") (name "/Fan_Ss") (class "Default")
      (node (ref "D17") (pin "3") (pinfunction "K_3") (pintype "passive"))
      (node (ref "J5") (pin "12") (pinfunction "12_12") (pintype "passive"))
      (node (ref "R87") (pin "2") (pinfunction "2_2") (pintype "passive"))
    )
    (net (code "11") (name "/L_Out") (class "Default")
      (node (ref "J5") (pin "5") (pinfunction "5_5") (pintype "passive"))
      (node (ref "R26") (pin "2") (pinfunction "2_2") (pintype "passive"))
    )
    (net (code "12") (name "/N_Out") (class "Default")
      (node (ref "J5") (pin "6") (pinfunction "6_6") (pintype "passive"))
      (node (ref "R35") (pin "2") (pinfunction "2_2") (pintype "passive"))
    )
    (net (code "13") (name "/PE_Bus+") (class "Default")
      (node (ref "J5") (pin "4") (pinfunction "4_4") (pintype "passive"))
      (node (ref "R52") (pin "2") (pinfunction "2_2") (pintype "passive"))
    )
    (net (code "14") (name "/PV+") (class "Default")
      (node (ref "J5") (pin "10") (pinfunction "10_10") (pintype "passive"))
      (node (ref "R132") (pin "1") (pinfunction "1_1") (pintype "passive"))
    )
    (net (code "15") (name "/PV-") (class "Default")
      (node (ref "J5") (pin "9") (pinfunction "9_9") (pintype "passive"))
      (node (ref "R139") (pin "1") (pinfunction "1_1") (pintype "passive"))
    )
    (net (code "16") (name "/RL-K1") (class "Default")
      (node (ref "K4") (pin "2") (pinfunction "2_2") (pintype "passive"))
      (node (ref "U1") (pin "13") (pinfunction "OUT4_13") (pintype "passive"))
      (node (ref "U1") (pin "14") (pinfunction "OUT3_14") (pintype "passive"))
    )
    (net (code "17") (name "/RL-K2") (class "Default")
      (node (ref "K3") (pin "2") (pinfunction "2_2") (pintype "passive"))
      (node (ref "U1") (pin "15") (pinfunction "OUT2_15") (pintype "passive"))
      (node (ref "U1") (pin "16") (pinfunction "OUT1_16") (pintype "passive"))
    )
    (net (code "18") (name "/RL-K3") (class "Default")
      (node (ref "K5") (pin "2") (pinfunction "2_2") (pintype "passive"))
      (node (ref "U1") (pin "12") (pinfunction "OUT5_12") (pintype "passive"))
    )
    (net (code "19") (name "/RL-K4") (class "Default")
      (node (ref "K1") (pin "2") (pinfunction "2_2") (pintype "passive"))
      (node (ref "U1") (pin "11") (pinfunction "OUT6_11") (pintype "passive"))
    )
    (net (code "20") (name "/Relay_1") (class "Default")
      (node (ref "J5") (pin "26") (pinfunction "26_26") (pintype "passive"))
      (node (ref "R10") (pin "1") (pinfunction "1_1") (pintype "passive"))
      (node (ref "R11") (pin "2") (pinfunction "2_2") (pintype "passive"))
      (node (ref "R9") (pin "2") (pinfunction "2_2") (pintype "passive"))
    )
    (net (code "21") (name "/Relay_2") (class "Default")
      (node (ref "J5") (pin "27") (pinfunction "27_27") (pintype "passive"))
      (node (ref "R12") (pin "2") (pinfunction "2_2") (pintype "passive"))
      (node (ref "R17") (pin "1") (pinfunction "1_1") (pintype "passive"))
      (node (ref "R18") (pin "2") (pinfunction "2_2") (pintype "passive"))
    )
    (net (code "22") (name "/Relay_3") (class "Default")
      (node (ref "J5") (pin "28") (pinfunction "28_28") (pintype "passive"))
      (node (ref "R21") (pin "2") (pinfunction "2_2") (pintype "passive"))
      (node (ref "R32") (pin "1") (pinfunction "1_1") (pintype "passive"))
    )
    (net (code "23") (name "/Relay_4") (class "Default")
      (node (ref "J5") (pin "25") (pinfunction "25_25") (pintype "passive"))
      (node (ref "R39") (pin "2") (pinfunction "2_2") (pintype "passive"))
      (node (ref "R42") (pin "1") (pinfunction "1_1") (pintype "passive"))
    )
    (net (code "24") (name "/Relay_5") (class "Default")
      (node (ref "J5") (pin "23") (pinfunction "23_23") (pintype "passive"))
      (node (ref "R51") (pin "2") (pinfunction "2_2") (pintype "passive"))
      (node (ref "R53") (pin "1") (pinfunction "1_1") (pintype "passive"))
    )
    (net (code "25") (name "/Ss_IPV") (class "Default")
      (node (ref "C68") (pin "1") (pinfunction "1_1") (pintype "passive"))
      (node (ref "J5") (pin "11") (pinfunction "11_11") (pintype "passive"))
      (node (ref "R102") (pin "2") (pinfunction "2_2") (pintype "passive"))
    )
    (net (code "26") (name "/Ss_Vout_EVN") (class "Default")
      (node (ref "J5") (pin "1") (pinfunction "1_1") (pintype "passive"))
      (node (ref "R6") (pin "1") (pinfunction "1_1") (pintype "passive"))
    )
    (net (code "27") (name "/Ss_Vref_ENV") (class "Default")
      (node (ref "J5") (pin "2") (pinfunction "2_2") (pintype "passive"))
      (node (ref "R7") (pin "1") (pinfunction "1_1") (pintype "passive"))
    )
    (net (code "28") (name "BAT +48") (class "Default")
      (node (ref "C20") (pin "2") (pinfunction "2_2") (pintype "passive"))
      (node (ref "C21") (pin "2") (pinfunction "2_2") (pintype "passive"))
      (node (ref "C22") (pin "1") (pinfunction "1_1") (pintype "passive"))
      (node (ref "C23") (pin "1") (pinfunction "1_1") (pintype "passive"))
      (node (ref "R127") (pin "2") (pinfunction "2_2") (pintype "passive"))
      (node (ref "R130") (pin "1") (pinfunction "1_1") (pintype "passive"))
      (node (ref "R63") (pin "2") (pinfunction "2_2") (pintype "passive"))
      (node (ref "R64") (pin "1") (pinfunction "1_1") (pintype "passive"))
      (node (ref "R82") (pin "1") (pinfunction "1_1") (pintype "passive"))
      (node (ref "T1") (pin "3") (pinfunction "3_3") (pintype "passive"))
    )
    (net (code "29") (name "BUS +") (class "Default")
      (node (ref "D9") (pin "1") (pinfunction "A_1") (pintype "passive"))
      (node (ref "K2") (pin "5") (pinfunction "5_5") (pintype "passive"))
      (node (ref "PV +1") (pin "1") (pinfunction "1_1") (pintype "passive"))
      (node (ref "R22") (pin "1") (pinfunction "1_1") (pintype "passive"))
    )
    (net (code "30") (name "BUS +10{slash}12V") (class "Default")
      (node (ref "C2") (pin "1") (pinfunction "1_1") (pintype "passive"))
      (node (ref "C4") (pin "2") (pinfunction "2_2") (pintype "passive"))
      (node (ref "C5") (pin "2") (pinfunction "2_2") (pintype "passive"))
      (node (ref "D1") (pin "2") (pinfunction "K_2") (pintype "passive"))
      (node (ref "D2") (pin "2") (pinfunction "A_2") (pintype "passive"))
      (node (ref "K1") (pin "3") (pinfunction "3_3") (pintype "passive"))
      (node (ref "K3") (pin "3") (pinfunction "3_3") (pintype "passive"))
      (node (ref "K4") (pin "3") (pinfunction "3_3") (pintype "passive"))
      (node (ref "Q1") (pin "2") (pinfunction "C_2") (pintype "passive"))
      (node (ref "R5") (pin "2") (pinfunction "2_2") (pintype "passive"))
    )
    (net (code "31") (name "GND") (class "Default")
      (node (ref "C4") (pin "1") (pinfunction "1_1") (pintype "passive"))
      (node (ref "C5") (pin "1") (pinfunction "1_1") (pintype "passive"))
      (node (ref "C6") (pin "1") (pinfunction "1_1") (pintype "passive"))
      (node (ref "C7") (pin "1") (pinfunction "1_1") (pintype "passive"))
      (node (ref "J5") (pin "19") (pinfunction "19_19") (pintype "passive"))
      (node (ref "Q2") (pin "3") (pinfunction "E_3") (pintype "passive"))
      (node (ref "R10") (pin "2") (pinfunction "2_2") (pintype "passive"))
      (node (ref "R17") (pin "2") (pinfunction "2_2") (pintype "passive"))
      (node (ref "R32") (pin "2") (pinfunction "2_2") (pintype "passive"))
      (node (ref "R42") (pin "2") (pinfunction "2_2") (pintype "passive"))
      (node (ref "R53") (pin "2") (pinfunction "2_2") (pintype "passive"))
      (node (ref "U1") (pin "8") (pinfunction "GND_8") (pintype "passive"))
    )
    (net (code "32") (name "GND_BAT") (class "Default")
      (node (ref "C20") (pin "1") (pinfunction "1_1") (pintype "passive"))
      (node (ref "C21") (pin "1") (pinfunction "1_1") (pintype "passive"))
      (node (ref "C22") (pin "2") (pinfunction "2_2") (pintype "passive"))
      (node (ref "C36") (pin "2") (pinfunction "2_2") (pintype "passive"))
      (node (ref "C37") (pin "2") (pinfunction "2_2") (pintype "passive"))
      (node (ref "C39") (pin "2") (pinfunction "2_2") (pintype "passive"))
      (node (ref "C50") (pin "1") (pinfunction "1_1") (pintype "passive"))
      (node (ref "C51") (pin "1") (pinfunction "1_1") (pintype "passive"))
      (node (ref "C52") (pin "1") (pinfunction "1_1") (pintype "passive"))
      (node (ref "C69") (pin "2") (pinfunction "2_2") (pintype "passive"))
      (node (ref "C72") (pin "1") (pinfunction "1_1") (pintype "passive"))
      (node (ref "C77") (pin "1") (pinfunction "1_1") (pintype "passive"))
      (node (ref "C78") (pin "1") (pinfunction "1_1") (pintype "passive"))
      (node (ref "C79") (pin "1") (pinfunction "1_1") (pintype "passive"))
      (node (ref "C90") (pin "1") (pinfunction "1_1") (pintype "passive"))
      (node (ref "C93") (pin "2") (pinfunction "2_2") (pintype "passive"))
      (node (ref "D22") (pin "1") (pinfunction "A_1") (pintype "passive"))
      (node (ref "D24") (pin "3") (pinfunction "A_3") (pintype "passive"))
      (node (ref "P1") (pin "3") (pinfunction "3_3") (pintype "passive"))
      (node (ref "P1") (pin "4") (pinfunction "4_4") (pintype "passive"))
      (node (ref "Q4") (pin "3") (pinfunction "E_3") (pintype "passive"))
      (node (ref "Q5") (pin "3") (pinfunction "E_3") (pintype "passive"))
      (node (ref "R109") (pin "2") (pinfunction "2_2") (pintype "passive"))
      (node (ref "R119") (pin "2") (pinfunction "2_2") (pintype "passive"))
      (node (ref "R120") (pin "2") (pinfunction "2_2") (pintype "passive"))
      (node (ref "R121") (pin "2") (pinfunction "2_2") (pintype "passive"))
      (node (ref "R122") (pin "2") (pinfunction "2_2") (pintype "passive"))
      (node (ref "R125") (pin "2") (pinfunction "2_2") (pintype "passive"))
      (node (ref "R145") (pin "2") (pinfunction "2_2") (pintype "passive"))
      (node (ref "R88") (pin "2") (pinfunction "2_2") (pintype "passive"))
      (node (ref "T1") (pin "6") (pinfunction "6_6") (pintype "passive"))
      (node (ref "U6") (pin "5") (pinfunction "GND_5") (pintype "passive"))
    )
    (net (code "33") (name "GND_FB") (class "Default")
      (node (ref "C1") (pin "2") (pinfunction "2_2") (pintype "passive"))
      (node (ref "C18") (pin "2") (pinfunction "2_2") (pintype "passive"))
      (node (ref "C2") (pin "2") (pinfunction "2_2") (pintype "passive"))
      (node (ref "C3") (pin "1") (pinfunction "1_1") (pintype "passive"))
      (node (ref "C38") (pin "1") (pinfunction "1_1") (pintype "passive"))
      (node (ref "C40") (pin "2") (pinfunction "2_2") (pintype "passive"))
      (node (ref "C41") (pin "2") (pinfunction "2_2") (pintype "passive"))
      (node (ref "C42") (pin "2") (pinfunction "2_2") (pintype "passive"))
      (node (ref "C43") (pin "2") (pinfunction "2_2") (pintype "passive"))
      (node (ref "C44") (pin "2") (pinfunction "2_2") (pintype "passive"))
      (node (ref "C45") (pin "2") (pinfunction "2_2") (pintype "passive"))
      (node (ref "C46") (pin "2") (pinfunction "2_2") (pintype "passive"))
      (node (ref "C47") (pin "2") (pinfunction "2_2") (pintype "passive"))
      (node (ref "C48") (pin "2") (pinfunction "2_2") (pintype "passive"))
      (node (ref "C53") (pin "1") (pinfunction "1_1") (pintype "passive"))
      (node (ref "C54") (pin "1") (pinfunction "1_1") (pintype "passive"))
      (node (ref "C55") (pin "1") (pinfunction "1_1") (pintype "passive"))
      (node (ref "C62") (pin "1") (pinfunction "1_1") (pintype "passive"))
      (node (ref "C63") (pin "1") (pinfunction "1_1") (pintype "passive"))
      (node (ref "C64") (pin "2") (pinfunction "2_2") (pintype "passive"))
      (node (ref "C65") (pin "2") (pinfunction "2_2") (pintype "passive"))
      (node (ref "C66") (pin "1") (pinfunction "1_1") (pintype "passive"))
      (node (ref "C67") (pin "1") (pinfunction "1_1") (pintype "passive"))
      (node (ref "C68") (pin "2") (pinfunction "2_2") (pintype "passive"))
      (node (ref "C73") (pin "2") (pinfunction "2_2") (pintype "passive"))
      (node (ref "C81") (pin "2") (pinfunction "2_2") (pintype "passive"))
      (node (ref "C82") (pin "2") (pinfunction "2_2") (pintype "passive"))
      (node (ref "C85") (pin "2") (pinfunction "2_2") (pintype "passive"))
      (node (ref "D16") (pin "2") (pinfunction "2_2") (pintype "passive"))
      (node (ref "H1") (pin "2") (pinfunction "2_2") (pintype "passive"))
      (node (ref "H2") (pin "2") (pinfunction "2_2") (pintype "passive"))
      (node (ref "J1") (pin "1") (pinfunction "1_1") (pintype "passive"))
      (node (ref "J5") (pin "14") (pinfunction "14_14") (pintype "passive"))
      (node (ref "L9") (pin "1") (pinfunction "1_1") (pintype "passive"))
      (node (ref "R123") (pin "2") (pinfunction "2_2") (pintype "passive"))
      (node (ref "R126") (pin "2") (pinfunction "2_2") (pintype "passive"))
      (node (ref "R128") (pin "1") (pinfunction "1_1") (pintype "passive"))
      (node (ref "R129") (pin "1") (pinfunction "1_1") (pintype "passive"))
      (node (ref "R5") (pin "1") (pinfunction "1_1") (pintype "passive"))
      (node (ref "R85") (pin "2") (pinfunction "2_2") (pintype "passive"))
      (node (ref "R87") (pin "1") (pinfunction "1_1") (pintype "passive"))
      (node (ref "T2") (pin "17") (pinfunction "17_17") (pintype "passive"))
      (node (ref "U10") (pin "13") (pinfunction "Gnd_13") (pintype "passive"))
      (node (ref "U3") (pin "1") (pinfunction "GND_1") (pintype "power_in"))
      (node (ref "U4") (pin "1") (pinfunction "GND_1") (pintype "power_in"))
      (node (ref "U7") (pin "5") (pinfunction "+INB_5") (pintype "input"))
      (node (ref "U9") (pin "3") (pinfunction "-_3") (pintype "passive"))
      (node (ref "V1") (pin "3") (pinfunction "E_3") (pintype "passive"))
      (node (ref "V2") (pin "3") (pinfunction "E_3") (pintype "passive"))
    )
    (net (code "34") (name "G_2") (class "Default")
      (node (ref "C33") (pin "1") (pinfunction "1_1") (pintype "passive"))
      (node (ref "C57") (pin "2") (pinfunction "2_2") (pintype "passive"))
      (node (ref "C59") (pin "1") (pinfunction "1_1") (pintype "passive"))
      (node (ref "C60") (pin "2") (pinfunction "2_2") (pintype "passive"))
      (node (ref "C61") (pin "2") (pinfunction "2_2") (pintype "passive"))
      (node (ref "C76") (pin "1") (pinfunction "1_1") (pintype "passive"))
      (node (ref "L6") (pin "2") (pinfunction "2_2") (pintype "passive"))
      (node (ref "L7") (pin "2") (pinfunction "2_2") (pintype "passive"))
      (node (ref "L8") (pin "2") (pinfunction "2_2") (pintype "passive"))
      (node (ref "R93") (pin "2") (pinfunction "2_2") (pintype "passive"))
      (node (ref "R94") (pin "2") (pinfunction "2_2") (pintype "passive"))
      (node (ref "R98") (pin "1") (pinfunction "1_1") (pintype "passive"))
      (node (ref "T2") (pin "5") (pinfunction "5_5") (pintype "passive"))
      (node (ref "U5") (pin "8") (pinfunction "GND_8") (pintype "passive"))
      (node (ref "U8") (pin "3") (pinfunction "3_3") (pintype "passive"))
    )
    (net (code "35") (name "NEG") (class "Default")
      (node (ref "*18") (pin "1") (pinfunction "1_1") (pintype "passive"))
      (node (ref "C89") (pin "1") (pinfunction "1_1") (pintype "passive"))
      (node (ref "C92") (pin "2") (pinfunction "2_2") (pintype "passive"))
      (node (ref "L11") (pin "2") (pinfunction "2_2") (pintype "passive"))
      (node (ref "L8") (pin "1") (pinfunction "1_1") (pintype "passive"))
      (node (ref "L9") (pin "2") (pinfunction "2_2") (pintype "passive"))
      (node (ref "R142") (pin "1") (pinfunction "1_1") (pintype "passive"))
      (node (ref "R58") (pin "2") (pinfunction "2_2") (pintype "passive"))
    )
    (net (code "36") (name "Net-(*2-Pad1)") (class "Default")
      (node (ref "*2") (pin "1") (pinfunction "1_1") (pintype "passive"))
      (node (ref "C12") (pin "1") (pinfunction "1_1") (pintype "passive"))
      (node (ref "C15") (pin "1") (pinfunction "1_1") (pintype "passive"))
      (node (ref "L5") (pin "2") (pinfunction "2_2") (pintype "passive"))
      (node (ref "R38") (pin "1") (pinfunction "1_1") (pintype "passive"))
      (node (ref "RV2") (pin "1") (pinfunction "1_1") (pintype "passive"))
      (node (ref "RV3") (pin "1") (pinfunction "1_1") (pintype "passive"))
    )
    (net (code "37") (name "Net-(*3-Pad1)") (class "Default")
      (node (ref "*3") (pin "1") (pinfunction "1_1") (pintype "passive"))
      (node (ref "L4") (pin "1") (pinfunction "1_1") (pintype "passive"))
    )
    (net (code "38") (name "Net-(*4-Pad1)") (class "Default")
      (node (ref "*4") (pin "1") (pinfunction "1_1") (pintype "passive"))
      (node (ref "C14") (pin "1") (pinfunction "1_1") (pintype "passive"))
      (node (ref "C9") (pin "2") (pinfunction "2_2") (pintype "passive"))
    )
    (net (code "39") (name "Net-(*5-Pad1)") (class "Default")
      (node (ref "*5") (pin "1") (pinfunction "1_1") (pintype "passive"))
      (node (ref "C10") (pin "2") (pinfunction "2_2") (pintype "passive"))
      (node (ref "C11") (pin "2") (pinfunction "2_2") (pintype "passive"))
      (node (ref "C16") (pin "1") (pinfunction "1_1") (pintype "passive"))
      (node (ref "C17") (pin "1") (pinfunction "1_1") (pintype "passive"))
    )
    (net (code "40") (name "Net-(*6-Pad1)") (class "Default")
      (node (ref "*6") (pin "1") (pinfunction "1_1") (pintype "passive"))
      (node (ref "C15") (pin "2") (pinfunction "2_2") (pintype "passive"))
      (node (ref "C8") (pin "2") (pinfunction "2_2") (pintype "passive"))
      (node (ref "D6") (pin "2") (pinfunction "2_2") (pintype "passive"))
    )
    (net (code "41") (name "Net-(*7-Pad1)") (class "Default")
      (node (ref "*7") (pin "1") (pinfunction "1_1") (pintype "passive"))
      (node (ref "L3") (pin "1") (pinfunction "1_1") (pintype "passive"))
    )
    (net (code "42") (name "Net-(*8-Pad1)") (class "Default")
      (node (ref "*8") (pin "1") (pinfunction "1_1") (pintype "passive"))
      (node (ref "C12") (pin "2") (pinfunction "2_2") (pintype "passive"))
      (node (ref "C8") (pin "1") (pinfunction "1_1") (pintype "passive"))
      (node (ref "L2") (pin "2") (pinfunction "2_2") (pintype "passive"))
      (node (ref "R29") (pin "1") (pinfunction "1_1") (pintype "passive"))
      (node (ref "RV1") (pin "1") (pinfunction "1_1") (pintype "passive"))
      (node (ref "RV2") (pin "2") (pinfunction "2_2") (pintype "passive"))
    )
    (net (code "43") (name "Net-(*9-Pad1)") (class "Default")
      (node (ref "*9") (pin "1") (pinfunction "1_1") (pintype "passive"))
      (node (ref "C16") (pin "2") (pinfunction "2_2") (pintype "passive"))
      (node (ref "C17") (pin "2") (pinfunction "2_2") (pintype "passive"))
      (node (ref "K4") (pin "4") (pinfunction "4_4") (pintype "passive"))
      (node (ref "K5") (pin "1") (pinfunction "1_1") (pintype "passive"))
      (node (ref "L4") (pin "2") (pinfunction "2_2") (pintype "passive"))
      (node (ref "R43") (pin "1") (pinfunction "1_1") (pintype "passive"))
      (node (ref "R50") (pin "2") (pinfunction "2_2") (pintype "passive"))
    )
    (net (code "44") (name "Net-(*10-Pad1)") (class "Default")
      (node (ref "*10") (pin "1") (pinfunction "1_1") (pintype "passive"))
      (node (ref "K5") (pin "4") (pinfunction "4_4") (pintype "passive"))
    )
    (net (code "45") (name "Net-(*11-Pad1)") (class "Default")
      (node (ref "*11") (pin "1") (pinfunction "1_1") (pintype "passive"))
      (node (ref "R59") (pin "1") (pinfunction "1_1") (pintype "passive"))
      (node (ref "R60") (pin "2") (pinfunction "2_2") (pintype "passive"))
    )
    (net (code "46") (name "Net-(*12-Pad1)") (class "Default")
      (node (ref "*12") (pin "1") (pinfunction "1_1") (pintype "passive"))
      (node (ref "C34") (pin "1") (pinfunction "1_1") (pintype "passive"))
      (node (ref "C35") (pin "1") (pinfunction "1_1") (pintype "passive"))
      (node (ref "C36") (pin "1") (pinfunction "1_1") (pintype "passive"))
      (node (ref "C37") (pin "1") (pinfunction "1_1") (pintype "passive"))
    )
    (net (code "47") (name "Net-(*13-Pad1)") (class "Default")
      (node (ref "*13") (pin "1") (pinfunction "1_1") (pintype "passive"))
      (node (ref "C87") (pin "2") (pinfunction "2_2") (pintype "passive"))
      (node (ref "C88") (pin "2") (pinfunction "2_2") (pintype "passive"))
      (node (ref "L10") (pin "1") (pinfunction "1_1") (pintype "passive"))
      (node (ref "R131") (pin "1") (pinfunction "1_1") (pintype "passive"))
      (node (ref "RV4") (pin "2") (pinfunction "2_2") (pintype "passive"))
    )
    (net (code "48") (name "Net-(*15-Pad1)") (class "Default")
      (node (ref "*15") (pin "1") (pinfunction "1_1") (pintype "passive"))
      (node (ref "C87") (pin "1") (pinfunction "1_1") (pintype "passive"))
      (node (ref "C91") (pin "1") (pinfunction "1_1") (pintype "passive"))
    )
    (net (code "49") (name "Net-(*16-Pad1)") (class "Default")
      (node (ref "*16") (pin "1") (pinfunction "1_1") (pintype "passive"))
      (node (ref "C86") (pin "1") (pinfunction "1_1") (pintype "passive"))
      (node (ref "C92") (pin "1") (pinfunction "1_1") (pintype "passive"))
    )
    (net (code "50") (name "Net-(*17-Pad1)") (class "Default")
      (node (ref "*17") (pin "1") (pinfunction "1_1") (pintype "passive"))
      (node (ref "C88") (pin "1") (pinfunction "1_1") (pintype "passive"))
      (node (ref "C91") (pin "2") (pinfunction "2_2") (pintype "passive"))
      (node (ref "L11") (pin "1") (pinfunction "1_1") (pintype "passive"))
      (node (ref "R144") (pin "1") (pinfunction "1_1") (pintype "passive"))
      (node (ref "RV4") (pin "1") (pinfunction "1_1") (pintype "passive"))
    )
    (net (code "51") (name "Net-(1-Pad2)") (class "Default")
      (node (ref "1") (pin "2") (pinfunction "2_2") (pintype "passive"))
      (node (ref "C70") (pin "2") (pinfunction "2_2") (pintype "passive"))
      (node (ref "R104") (pin "1") (pinfunction "1_1") (pintype "passive"))
    )
    (net (code "52") (name "Net-(C13-Pad1)") (class "Default")
      (node (ref "C13") (pin "1") (pinfunction "1_1") (pintype "passive"))
      (node (ref "C14") (pin "2") (pinfunction "2_2") (pintype "passive"))
      (node (ref "K4") (pin "1") (pinfunction "1_1") (pintype "passive"))
      (node (ref "L5") (pin "1") (pinfunction "1_1") (pintype "passive"))
      (node (ref "R49") (pin "2") (pinfunction "2_2") (pintype "passive"))
    )
    (net (code "53") (name "Net-(C13-Pad2)") (class "Default")
      (node (ref "C13") (pin "2") (pinfunction "2_2") (pintype "passive"))
      (node (ref "C9") (pin "1") (pinfunction "1_1") (pintype "passive"))
      (node (ref "K3") (pin "4") (pinfunction "4_4") (pintype "passive"))
      (node (ref "L2") (pin "1") (pinfunction "1_1") (pintype "passive"))
      (node (ref "R19") (pin "1") (pinfunction "1_1") (pintype "passive"))
    )
    (net (code "54") (name "Net-(C19-Pad2)") (class "Default")
      (node (ref "C19") (pin "2") (pinfunction "2_2") (pintype "passive"))
      (node (ref "R61") (pin "1") (pinfunction "1_1") (pintype "passive"))
      (node (ref "R62") (pin "1") (pinfunction "1_1") (pintype "passive"))
    )
    (net (code "55") (name "Net-(C24-Pad2)") (class "Default")
      (node (ref "C24") (pin "2") (pinfunction "2_2") (pintype "passive"))
      (node (ref "R65") (pin "1") (pinfunction "1_1") (pintype "passive"))
    )
    (net (code "56") (name "Net-(C25-Pad2)") (class "Default")
      (node (ref "C25") (pin "2") (pinfunction "2_2") (pintype "passive"))
      (node (ref "C26") (pin "2") (pinfunction "2_2") (pintype "passive"))
      (node (ref "C27") (pin "2") (pinfunction "2_2") (pintype "passive"))
      (node (ref "C28") (pin "2") (pinfunction "2_2") (pintype "passive"))
      (node (ref "J2") (pin "1") (pinfunction "1_1") (pintype "passive"))
      (node (ref "R67") (pin "2") (pinfunction "2_2") (pintype "passive"))
      (node (ref "T2") (pin "21") (pinfunction "21_21") (pintype "passive"))
    )
    (net (code "57") (name "Net-(C30-Pad2)") (class "Default")
      (node (ref "C30") (pin "2") (pinfunction "2_2") (pintype "passive"))
      (node (ref "C31") (pin "2") (pinfunction "2_2") (pintype "passive"))
      (node (ref "C32") (pin "2") (pinfunction "2_2") (pintype "passive"))
      (node (ref "C39") (pin "1") (pinfunction "1_1") (pintype "passive"))
      (node (ref "L6") (pin "1") (pinfunction "1_1") (pintype "passive"))
      (node (ref "R68") (pin "2") (pinfunction "2_2") (pintype "passive"))
      (node (ref "T1") (pin "9") (pinfunction "9_9") (pintype "passive"))
    )
    (net (code "58") (name "Net-(C49-Pad1)") (class "Default")
      (node (ref "C49") (pin "1") (pinfunction "1_1") (pintype "passive"))
      (node (ref "R79") (pin "2") (pinfunction "2_2") (pintype "passive"))
    )
    (net (code "59") (name "Net-(C56-Pad1)") (class "Default")
      (node (ref "C56") (pin "1") (pinfunction "1_1") (pintype "passive"))
      (node (ref "R90") (pin "2") (pinfunction "2_2") (pintype "passive"))
    )
    (net (code "60") (name "Net-(C58-Pad1)") (class "Default")
      (node (ref "C58") (pin "1") (pinfunction "1_1") (pintype "passive"))
      (node (ref "R91") (pin "2") (pinfunction "2_2") (pintype "passive"))
    )
    (net (code "61") (name "Net-(C70-Pad1)") (class "Default")
      (node (ref "C70") (pin "1") (pinfunction "1_1") (pintype "passive"))
      (node (ref "R104") (pin "2") (pinfunction "2_2") (pintype "passive"))
      (node (ref "R117") (pin "2") (pinfunction "2_2") (pintype "passive"))
      (node (ref "R125") (pin "1") (pinfunction "1_1") (pintype "passive"))
    )
    (net (code "62") (name "Net-(C75-Pad1)") (class "Default")
      (node (ref "C75") (pin "1") (pinfunction "1_1") (pintype "passive"))
      (node (ref "R117") (pin "1") (pinfunction "1_1") (pintype "passive"))
      (node (ref "R118") (pin "2") (pinfunction "2_2") (pintype "passive"))
    )
    (net (code "63") (name "Net-(C80-Pad2)") (class "Default")
      (node (ref "C80") (pin "2") (pinfunction "2_2") (pintype "passive"))
      (node (ref "C84") (pin "1") (pinfunction "1_1") (pintype "passive"))
      (node (ref "R124") (pin "2") (pinfunction "2_2") (pintype "passive"))
    )
    (net (code "64") (name "Net-(D2-K)") (class "Default")
      (node (ref "D2") (pin "1") (pinfunction "K_1") (pintype "passive"))
      (node (ref "D5") (pin "2") (pinfunction "A_2") (pintype "passive"))
    )
    (net (code "65") (name "Net-(D3-A1)") (class "Default")
      (node (ref "D3") (pin "1") (pinfunction "A1_1") (pintype "passive"))
      (node (ref "D3") (pin "2") (pinfunction "A2_2") (pintype "passive"))
      (node (ref "D4") (pin "1") (pinfunction "A1_1") (pintype "passive"))
      (node (ref "D4") (pin "2") (pinfunction "A2_2") (pintype "passive"))
      (node (ref "K2") (pin "12") (pinfunction "12_12") (pintype "passive"))
    )
    (net (code "66") (name "Net-(D3-K)") (class "Default")
      (node (ref "D3") (pin "3") (pinfunction "K_3") (pintype "passive"))
      (node (ref "U1") (pin "10") (pinfunction "OUT7_10") (pintype "passive"))
    )
    (net (code "67") (name "Net-(D5-K)") (class "Default")
      (node (ref "C6") (pin "2") (pinfunction "2_2") (pintype "passive"))
      (node (ref "C7") (pin "2") (pinfunction "2_2") (pintype "passive"))
      (node (ref "D5") (pin "1") (pinfunction "K_1") (pintype "passive"))
      (node (ref "U1") (pin "9") (pinfunction "COM_9") (pintype "passive"))
    )
    (net (code "68") (name "Net-(D6-Pad1)") (class "Default")
      (node (ref "D6") (pin "1") (pinfunction "1_1") (pintype "passive"))
      (node (ref "RV1") (pin "2") (pinfunction "2_2") (pintype "passive"))
      (node (ref "RV3") (pin "2") (pinfunction "2_2") (pintype "passive"))
    )
    (net (code "69") (name "Net-(D7-A)") (class "Default")
      (node (ref "C24") (pin "1") (pinfunction "1_1") (pintype "passive"))
      (node (ref "D7") (pin "1") (pinfunction "A_1") (pintype "passive"))
      (node (ref "D7") (pin "2") (pinfunction "NC_2") (pintype "passive"))
      (node (ref "T2") (pin "23") (pinfunction "23_23") (pintype "passive"))
    )
    (net (code "70") (name "Net-(D7-K)") (class "Default")
      (node (ref "C25") (pin "1") (pinfunction "1_1") (pintype "passive"))
      (node (ref "C26") (pin "1") (pinfunction "1_1") (pintype "passive"))
      (node (ref "C27") (pin "1") (pinfunction "1_1") (pintype "passive"))
      (node (ref "C28") (pin "1") (pinfunction "1_1") (pintype "passive"))
      (node (ref "D7") (pin "3") (pinfunction "K_3") (pintype "passive"))
      (node (ref "J2") (pin "2") (pinfunction "2_2") (pintype "passive"))
      (node (ref "R65") (pin "2") (pinfunction "2_2") (pintype "passive"))
      (node (ref "R67") (pin "1") (pinfunction "1_1") (pintype "passive"))
    )
    (net (code "71") (name "Net-(D8-A)") (class "Default")
      (node (ref "C34") (pin "2") (pinfunction "2_2") (pintype "passive"))
      (node (ref "C35") (pin "2") (pinfunction "2_2") (pintype "passive"))
      (node (ref "D8") (pin "1") (pinfunction "A_1") (pintype "passive"))
      (node (ref "P1") (pin "1") (pinfunction "1_1") (pintype "passive"))
      (node (ref "P1") (pin "2") (pinfunction "2_2") (pintype "passive"))
    )
    (net (code "72") (name "Net-(D8-K)") (class "Default")
      (node (ref "D8") (pin "2") (pinfunction "K_2") (pintype "passive"))
      (node (ref "R63") (pin "1") (pinfunction "1_1") (pintype "passive"))
    )
    (net (code "73") (name "Net-(D10-K)") (class "Default")
      (node (ref "C29") (pin "2") (pinfunction "2_2") (pintype "passive"))
      (node (ref "C33") (pin "2") (pinfunction "2_2") (pintype "passive"))
      (node (ref "D10") (pin "2") (pinfunction "K_2") (pintype "passive"))
      (node (ref "D11") (pin "2") (pinfunction "K_2") (pintype "passive"))
      (node (ref "D9") (pin "2") (pinfunction "K_2") (pintype "passive"))
      (node (ref "R70") (pin "2") (pinfunction "2_2") (pintype "passive"))
      (node (ref "R78") (pin "2") (pinfunction "2_2") (pintype "passive"))
      (node (ref "T2") (pin "1") (pinfunction "1_1") (pintype "passive"))
    )
    (net (code "74") (name "Net-(D11-A)") (class "Default")
      (node (ref "C30") (pin "1") (pinfunction "1_1") (pintype "passive"))
      (node (ref "C31") (pin "1") (pinfunction "1_1") (pintype "passive"))
      (node (ref "C32") (pin "1") (pinfunction "1_1") (pintype "passive"))
      (node (ref "D11") (pin "1") (pinfunction "A_1") (pintype "passive"))
      (node (ref "D12") (pin "2") (pinfunction "K_2") (pintype "passive"))
      (node (ref "R61") (pin "2") (pinfunction "2_2") (pintype "passive"))
      (node (ref "R62") (pin "2") (pinfunction "2_2") (pintype "passive"))
      (node (ref "R68") (pin "1") (pinfunction "1_1") (pintype "passive"))
    )
    (net (code "75") (name "Net-(D12-A)") (class "Default")
      (node (ref "C19") (pin "1") (pinfunction "1_1") (pintype "passive"))
      (node (ref "D12") (pin "1") (pinfunction "A_1") (pintype "passive"))
      (node (ref "T1") (pin "8") (pinfunction "8_8") (pintype "passive"))
    )
    (net (code "76") (name "Net-(D13-A)") (class "Default")
      (node (ref "D13") (pin "1") (pinfunction "A_1") (pintype "passive"))
      (node (ref "Q3") (pin "2") (pinfunction "D_2") (pintype "passive"))
      (node (ref "T1") (pin "4") (pinfunction "4_4") (pintype "passive"))
    )
    (net (code "77") (name "Net-(D13-K)") (class "Default")
      (node (ref "C23") (pin "2") (pinfunction "2_2") (pintype "passive"))
      (node (ref "D13") (pin "2") (pinfunction "K_2") (pintype "passive"))
      (node (ref "R69") (pin "1") (pinfunction "1_1") (pintype "passive"))
    )
    (net (code "78") (name "Net-(D14-A)") (class "Default")
      (node (ref "D14") (pin "1") (pinfunction "A_1") (pintype "passive"))
      (node (ref "T2") (pin "3") (pinfunction "3_3") (pintype "passive"))
      (node (ref "U5") (pin "5") (pinfunction "DRAIN_5") (pintype "passive"))
    )
    (net (code "79") (name "Net-(D14-K)") (class "Default")
      (node (ref "C29") (pin "1") (pinfunction "1_1") (pintype "passive"))
      (node (ref "D14") (pin "2") (pinfunction "K_2") (pintype "passive"))
      (node (ref "R75") (pin "1") (pinfunction "1_1") (pintype "passive"))
    )
    (net (code "80") (name "Net-(D15-A)") (class "Default")
      (node (ref "C49") (pin "2") (pinfunction "2_2") (pintype "passive"))
      (node (ref "D15") (pin "1") (pinfunction "A_1") (pintype "passive"))
      (node (ref "D15") (pin "2") (pinfunction "NC_2") (pintype "passive"))
      (node (ref "T2") (pin "19") (pinfunction "19_19") (pintype "passive"))
    )
    (net (code "81") (name "Net-(D16-Pad1)") (class "Default")
      (node (ref "D16") (pin "1") (pinfunction "1_1") (pintype "passive"))
      (node (ref "R77") (pin "1") (pinfunction "1_1") (pintype "passive"))
    )
    (net (code "82") (name "Net-(D17-A1)") (class "Default")
      (node (ref "C66") (pin "2") (pinfunction "2_2") (pintype "passive"))
      (node (ref "D17") (pin "1") (pinfunction "A1_1") (pintype "passive"))
      (node (ref "H2") (pin "3") (pinfunction "3_3") (pintype "passive"))
      (node (ref "R96") (pin "1") (pinfunction "1_1") (pintype "passive"))
    )
    (net (code "83") (name "Net-(D17-A2)") (class "Default")
      (node (ref "C38") (pin "2") (pinfunction "2_2") (pintype "passive"))
      (node (ref "D17") (pin "2") (pinfunction "A2_2") (pintype "passive"))
      (node (ref "H1") (pin "3") (pinfunction "3_3") (pintype "passive"))
      (node (ref "R66") (pin "1") (pinfunction "1_1") (pintype "passive"))
    )
    (net (code "84") (name "Net-(D18-A1)") (class "Default")
      (node (ref "1") (pin "1") (pinfunction "1_1") (pintype "passive"))
      (node (ref "C51") (pin "2") (pinfunction "2_2") (pintype "passive"))
      (node (ref "C52") (pin "2") (pinfunction "2_2") (pintype "passive"))
      (node (ref "D18") (pin "1") (pinfunction "A1_1") (pintype "passive"))
      (node (ref "D18") (pin "2") (pinfunction "A2_2") (pintype "passive"))
      (node (ref "D19") (pin "2") (pinfunction "K_2") (pintype "passive"))
      (node (ref "R88") (pin "1") (pinfunction "1_1") (pintype "passive"))
    )
    (net (code "85") (name "Net-(D18-K)") (class "Default")
      (node (ref "D18") (pin "3") (pinfunction "K_3") (pintype "passive"))
      (node (ref "R84") (pin "2") (pinfunction "2_2") (pintype "passive"))
    )
    (net (code "86") (name "Net-(D19-A)") (class "Default")
      (node (ref "D19") (pin "1") (pinfunction "A_1") (pintype "passive"))
      (node (ref "T1") (pin "5") (pinfunction "5_5") (pintype "passive"))
    )
    (net (code "87") (name "Net-(D20-A)") (class "Default")
      (node (ref "D20") (pin "1") (pinfunction "A_1") (pintype "passive"))
      (node (ref "T2") (pin "7") (pinfunction "7_7") (pintype "passive"))
    )
    (net (code "88") (name "Net-(D20-K)") (class "Default")
      (node (ref "D20") (pin "2") (pinfunction "K_2") (pintype "passive"))
      (node (ref "R89") (pin "1") (pinfunction "1_1") (pintype "passive"))
    )
    (net (code "89") (name "Net-(D21-A)") (class "Default")
      (node (ref "C53") (pin "2") (pinfunction "2_2") (pintype "passive"))
      (node (ref "C54") (pin "2") (pinfunction "2_2") (pintype "passive"))
      (node (ref "D21") (pin "1") (pinfunction "A_1") (pintype "passive"))
      (node (ref "R90") (pin "1") (pinfunction "1_1") (pintype "passive"))
      (node (ref "U4") (pin "2") (pinfunction "IN_2") (pintype "power_in"))
    )
    (net (code "90") (name "Net-(D21-K)") (class "Default")
      (node (ref "C56") (pin "2") (pinfunction "2_2") (pintype "passive"))
      (node (ref "D21") (pin "2") (pinfunction "K_2") (pintype "passive"))
      (node (ref "T2") (pin "15") (pinfunction "15_15") (pintype "passive"))
    )
    (net (code "91") (name "Net-(D22-K)") (class "Default")
      (node (ref "C50") (pin "2") (pinfunction "2_2") (pintype "passive"))
      (node (ref "D22") (pin "3") (pinfunction "K_3") (pintype "passive"))
      (node (ref "J4") (pin "2") (pinfunction "2_2") (pintype "passive"))
      (node (ref "R83") (pin "2") (pinfunction "2_2") (pintype "passive"))
      (node (ref "R84") (pin "1") (pinfunction "1_1") (pintype "passive"))
      (node (ref "R95") (pin "1") (pinfunction "1_1") (pintype "passive"))
    )
    (net (code "92") (name "Net-(D23-A)") (class "Default")
      (node (ref "C58") (pin "2") (pinfunction "2_2") (pintype "passive"))
      (node (ref "D23") (pin "1") (pinfunction "A_1") (pintype "passive"))
      (node (ref "D23") (pin "2") (pinfunction "NC_2") (pintype "passive"))
      (node (ref "T2") (pin "13") (pinfunction "13_13") (pintype "passive"))
    )
    (net (code "93") (name "Net-(D25-A)") (class "Default")
      (node (ref "D25") (pin "1") (pinfunction "A_1") (pintype "passive"))
      (node (ref "D27") (pin "3") (pinfunction "K_3") (pintype "passive"))
    )
    (net (code "94") (name "Net-(D25-K)") (class "Default")
      (node (ref "D25") (pin "3") (pinfunction "K_3") (pintype "passive"))
      (node (ref "R127") (pin "1") (pinfunction "1_1") (pintype "passive"))
    )
    (net (code "95") (name "Net-(D26-A)") (class "Default")
      (node (ref "C90") (pin "2") (pinfunction "2_2") (pintype "passive"))
      (node (ref "D26") (pin "3") (pinfunction "A_3") (pintype "passive"))
      (node (ref "R136") (pin "2") (pinfunction "2_2") (pintype "passive"))
    )
    (net (code "96") (name "Net-(D27-A)") (class "Default")
      (node (ref "C93") (pin "1") (pinfunction "1_1") (pintype "passive"))
      (node (ref "D27") (pin "1") (pinfunction "A_1") (pintype "passive"))
      (node (ref "Q5") (pin "1") (pinfunction "B_1") (pintype "passive"))
      (node (ref "R145") (pin "1") (pinfunction "1_1") (pintype "passive"))
    )
    (net (code "97") (name "Net-(J3-Pad1)") (class "Default")
      (node (ref "J3") (pin "1") (pinfunction "1_1") (pintype "passive"))
      (node (ref "T2") (pin "11") (pinfunction "11_11") (pintype "passive"))
    )
    (net (code "98") (name "Net-(J3-Pad2)") (class "Default")
      (node (ref "J3") (pin "2") (pinfunction "2_2") (pintype "passive"))
      (node (ref "T2") (pin "9") (pinfunction "9_9") (pintype "passive"))
    )
    (net (code "99") (name "Net-(J5-Pad21)") (class "Default")
      (node (ref "J5") (pin "21") (pinfunction "21_21") (pintype "passive"))
      (node (ref "R143") (pin "2") (pinfunction "2_2") (pintype "passive"))
    )
    (net (code "100") (name "Net-(J5-Pad29)") (class "Default")
      (node (ref "J5") (pin "29") (pinfunction "29_29") (pintype "passive"))
      (node (ref "R146") (pin "2") (pinfunction "2_2") (pintype "passive"))
    )
    (net (code "101") (name "Net-(J5-Pad30)") (class "Default")
      (node (ref "J5") (pin "30") (pinfunction "30_30") (pintype "passive"))
      (node (ref "R147") (pin "1") (pinfunction "1_1") (pintype "passive"))
    )
    (net (code "102") (name "Net-(K1-Pad4)") (class "Default")
      (node (ref "K1") (pin "4") (pinfunction "4_4") (pintype "passive"))
      (node (ref "K3") (pin "1") (pinfunction "1_1") (pintype "passive"))
      (node (ref "L3") (pin "2") (pinfunction "2_2") (pintype "passive"))
    )
    (net (code "103") (name "Net-(K2-Pad1)") (class "Default")
      (node (ref "K2") (pin "1") (pinfunction "1_1") (pintype "passive"))
      (node (ref "R8") (pin "2") (pinfunction "2_2") (pintype "passive"))
    )
    (net (code "104") (name "Net-(K2-Pad4)") (class "Default")
      (node (ref "K2") (pin "4") (pinfunction "4_4") (pintype "passive"))
      (node (ref "K2") (pin "9") (pinfunction "9_9") (pintype "passive"))
    )
    (net (code "105") (name "Net-(K2-Pad8)") (class "Default")
      (node (ref "K2") (pin "8") (pinfunction "8_8") (pintype "passive"))
      (node (ref "R25") (pin "2") (pinfunction "2_2") (pintype "passive"))
      (node (ref "R33") (pin "1") (pinfunction "1_1") (pintype "passive"))
      (node (ref "R34") (pin "1") (pinfunction "1_1") (pintype "passive"))
    )
    (net (code "106") (name "Net-(Q1-B)") (class "Default")
      (node (ref "Q1") (pin "1") (pinfunction "B_1") (pintype "passive"))
      (node (ref "R2") (pin "1") (pinfunction "1_1") (pintype "passive"))
      (node (ref "R3") (pin "2") (pinfunction "2_2") (pintype "passive"))
    )
    (net (code "107") (name "Net-(Q1-E)") (class "Default")
      (node (ref "C1") (pin "1") (pinfunction "1_1") (pintype "passive"))
      (node (ref "L1") (pin "2") (pinfunction "2_2") (pintype "passive"))
      (node (ref "Q1") (pin "3") (pinfunction "E_3") (pintype "passive"))
      (node (ref "R1") (pin "2") (pinfunction "2_2") (pintype "passive"))
    )
    (net (code "108") (name "Net-(Q2-B)") (class "Default")
      (node (ref "Q2") (pin "1") (pinfunction "B_1") (pintype "passive"))
      (node (ref "R4") (pin "2") (pinfunction "2_2") (pintype "passive"))
    )
    (net (code "109") (name "Net-(Q2-C)") (class "Default")
      (node (ref "Q2") (pin "2") (pinfunction "C_2") (pintype "passive"))
      (node (ref "R1") (pin "1") (pinfunction "1_1") (pintype "passive"))
      (node (ref "R2") (pin "2") (pinfunction "2_2") (pintype "passive"))
      (node (ref "R3") (pin "1") (pinfunction "1_1") (pintype "passive"))
    )
    (net (code "110") (name "Net-(Q3-G)") (class "Default")
      (node (ref "Q3") (pin "1") (pinfunction "G_1") (pintype "passive"))
      (node (ref "R103") (pin "1") (pinfunction "1_1") (pintype "passive"))
      (node (ref "R109") (pin "1") (pinfunction "1_1") (pintype "passive"))
    )
    (net (code "111") (name "Net-(Q3-S)") (class "Default")
      (node (ref "Q3") (pin "3") (pinfunction "S_3") (pintype "passive"))
      (node (ref "R110") (pin "1") (pinfunction "1_1") (pintype "passive"))
      (node (ref "R119") (pin "1") (pinfunction "1_1") (pintype "passive"))
      (node (ref "R120") (pin "1") (pinfunction "1_1") (pintype "passive"))
      (node (ref "R121") (pin "1") (pinfunction "1_1") (pintype "passive"))
      (node (ref "R122") (pin "1") (pinfunction "1_1") (pintype "passive"))
    )
    (net (code "112") (name "Net-(Q4-B)") (class "Default")
      (node (ref "Q4") (pin "1") (pinfunction "B_1") (pintype "passive"))
      (node (ref "Q5") (pin "2") (pinfunction "C_2") (pintype "passive"))
      (node (ref "R130") (pin "2") (pinfunction "2_2") (pintype "passive"))
    )
    (net (code "113") (name "Net-(Q4-C)") (class "Default")
      (node (ref "C74") (pin "1") (pinfunction "1_1") (pintype "passive"))
      (node (ref "C75") (pin "2") (pinfunction "2_2") (pintype "passive"))
      (node (ref "D26") (pin "1") (pinfunction "C_1") (pintype "passive"))
      (node (ref "Q4") (pin "2") (pinfunction "C_2") (pintype "passive"))
      (node (ref "U6") (pin "1") (pinfunction "COMP_1") (pintype "input"))
    )
    (net (code "114") (name "Net-(R13-Pad2)") (class "Default")
      (node (ref "R13") (pin "2") (pinfunction "2_2") (pintype "passive"))
      (node (ref "R14") (pin "1") (pinfunction "1_1") (pintype "passive"))
    )
    (net (code "115") (name "Net-(R14-Pad2)") (class "Default")
      (node (ref "R14") (pin "2") (pinfunction "2_2") (pintype "passive"))
      (node (ref "R15") (pin "1") (pinfunction "1_1") (pintype "passive"))
    )
    (net (code "116") (name "Net-(R15-Pad2)") (class "Default")
      (node (ref "R15") (pin "2") (pinfunction "2_2") (pintype "passive"))
      (node (ref "R16") (pin "1") (pinfunction "1_1") (pintype "passive"))
    )
    (net (code "117") (name "Net-(R19-Pad2)") (class "Default")
      (node (ref "R19") (pin "2") (pinfunction "2_2") (pintype "passive"))
      (node (ref "R30") (pin "1") (pinfunction "1_1") (pintype "passive"))
    )
    (net (code "118") (name "Net-(R20-Pad2)") (class "Default")
      (node (ref "R20") (pin "2") (pinfunction "2_2") (pintype "passive"))
      (node (ref "R31") (pin "1") (pinfunction "1_1") (pintype "passive"))
    )
    (net (code "119") (name "Net-(R22-Pad2)") (class "Default")
      (node (ref "R22") (pin "2") (pinfunction "2_2") (pintype "passive"))
      (node (ref "R23") (pin "1") (pinfunction "1_1") (pintype "passive"))
    )
    (net (code "120") (name "Net-(R23-Pad2)") (class "Default")
      (node (ref "R23") (pin "2") (pinfunction "2_2") (pintype "passive"))
      (node (ref "R24") (pin "1") (pinfunction "1_1") (pintype "passive"))
    )
    (net (code "121") (name "Net-(R24-Pad2)") (class "Default")
      (node (ref "R24") (pin "2") (pinfunction "2_2") (pintype "passive"))
      (node (ref "R25") (pin "1") (pinfunction "1_1") (pintype "passive"))
    )
    (net (code "122") (name "Net-(R26-Pad1)") (class "Default")
      (node (ref "R26") (pin "1") (pinfunction "1_1") (pintype "passive"))
      (node (ref "R27") (pin "2") (pinfunction "2_2") (pintype "passive"))
    )
    (net (code "123") (name "Net-(R27-Pad1)") (class "Default")
      (node (ref "R27") (pin "1") (pinfunction "1_1") (pintype "passive"))
      (node (ref "R28") (pin "2") (pinfunction "2_2") (pintype "passive"))
    )
    (net (code "124") (name "Net-(R28-Pad1)") (class "Default")
      (node (ref "R28") (pin "1") (pinfunction "1_1") (pintype "passive"))
      (node (ref "R29") (pin "2") (pinfunction "2_2") (pintype "passive"))
    )
    (net (code "125") (name "Net-(R30-Pad2)") (class "Default")
      (node (ref "R30") (pin "2") (pinfunction "2_2") (pintype "passive"))
      (node (ref "R40") (pin "1") (pinfunction "1_1") (pintype "passive"))
    )
    (net (code "126") (name "Net-(R31-Pad2)") (class "Default")
      (node (ref "R31") (pin "2") (pinfunction "2_2") (pintype "passive"))
      (node (ref "R41") (pin "1") (pinfunction "1_1") (pintype "passive"))
    )
    (net (code "127") (name "Net-(R33-Pad2)") (class "Default")
      (node (ref "R33") (pin "2") (pinfunction "2_2") (pintype "passive"))
      (node (ref "R47") (pin "1") (pinfunction "1_1") (pintype "passive"))
    )
    (net (code "128") (name "Net-(R34-Pad2)") (class "Default")
      (node (ref "R34") (pin "2") (pinfunction "2_2") (pintype "passive"))
      (node (ref "R48") (pin "1") (pinfunction "1_1") (pintype "passive"))
    )
    (net (code "129") (name "Net-(R35-Pad1)") (class "Default")
      (node (ref "R35") (pin "1") (pinfunction "1_1") (pintype "passive"))
      (node (ref "R36") (pin "2") (pinfunction "2_2") (pintype "passive"))
    )
    (net (code "130") (name "Net-(R36-Pad1)") (class "Default")
      (node (ref "R36") (pin "1") (pinfunction "1_1") (pintype "passive"))
      (node (ref "R37") (pin "2") (pinfunction "2_2") (pintype "passive"))
    )
    (net (code "131") (name "Net-(R37-Pad1)") (class "Default")
      (node (ref "R37") (pin "1") (pinfunction "1_1") (pintype "passive"))
      (node (ref "R38") (pin "2") (pinfunction "2_2") (pintype "passive"))
    )
    (net (code "132") (name "Net-(R40-Pad2)") (class "Default")
      (node (ref "R40") (pin "2") (pinfunction "2_2") (pintype "passive"))
      (node (ref "R49") (pin "1") (pinfunction "1_1") (pintype "passive"))
    )
    (net (code "133") (name "Net-(R41-Pad2)") (class "Default")
      (node (ref "R41") (pin "2") (pinfunction "2_2") (pintype "passive"))
      (node (ref "R50") (pin "1") (pinfunction "1_1") (pintype "passive"))
    )
    (net (code "134") (name "Net-(R43-Pad2)") (class "Default")
      (node (ref "R43") (pin "2") (pinfunction "2_2") (pintype "passive"))
      (node (ref "R44") (pin "1") (pinfunction "1_1") (pintype "passive"))
    )
    (net (code "135") (name "Net-(R44-Pad2)") (class "Default")
      (node (ref "R44") (pin "2") (pinfunction "2_2") (pintype "passive"))
      (node (ref "R45") (pin "1") (pinfunction "1_1") (pintype "passive"))
    )
    (net (code "136") (name "Net-(R45-Pad2)") (class "Default")
      (node (ref "R45") (pin "2") (pinfunction "2_2") (pintype "passive"))
      (node (ref "R46") (pin "1") (pinfunction "1_1") (pintype "passive"))
    )
    (net (code "137") (name "Net-(R47-Pad2)") (class "Default")
      (node (ref "R47") (pin "2") (pinfunction "2_2") (pintype "passive"))
      (node (ref "R54") (pin "1") (pinfunction "1_1") (pintype "passive"))
    )
    (net (code "138") (name "Net-(R48-Pad2)") (class "Default")
      (node (ref "R48") (pin "2") (pinfunction "2_2") (pintype "passive"))
      (node (ref "R55") (pin "1") (pinfunction "1_1") (pintype "passive"))
    )
    (net (code "139") (name "Net-(R52-Pad1)") (class "Default")
      (node (ref "R52") (pin "1") (pinfunction "1_1") (pintype "passive"))
      (node (ref "R56") (pin "2") (pinfunction "2_2") (pintype "passive"))
    )
    (net (code "140") (name "Net-(R54-Pad2)") (class "Default")
      (node (ref "R54") (pin "2") (pinfunction "2_2") (pintype "passive"))
      (node (ref "R57") (pin "1") (pinfunction "1_1") (pintype "passive"))
    )
    (net (code "141") (name "Net-(R55-Pad2)") (class "Default")
      (node (ref "R55") (pin "2") (pinfunction "2_2") (pintype "passive"))
      (node (ref "R58") (pin "1") (pinfunction "1_1") (pintype "passive"))
    )
    (net (code "142") (name "Net-(R56-Pad1)") (class "Default")
      (node (ref "R56") (pin "1") (pinfunction "1_1") (pintype "passive"))
      (node (ref "R59") (pin "2") (pinfunction "2_2") (pintype "passive"))
    )
    (net (code "143") (name "Net-(R57-Pad2)") (class "Default")
      (node (ref "R57") (pin "2") (pinfunction "2_2") (pintype "passive"))
      (node (ref "R60") (pin "1") (pinfunction "1_1") (pintype "passive"))
    )
    (net (code "144") (name "Net-(R64-Pad2)") (class "Default")
      (node (ref "R64") (pin "2") (pinfunction "2_2") (pintype "passive"))
      (node (ref "R69") (pin "2") (pinfunction "2_2") (pintype "passive"))
    )
    (net (code "145") (name "Net-(R70-Pad1)") (class "Default")
      (node (ref "R70") (pin "1") (pinfunction "1_1") (pintype "passive"))
      (node (ref "R73") (pin "2") (pinfunction "2_2") (pintype "passive"))
    )
    (net (code "146") (name "Net-(R71-Pad1)") (class "Default")
      (node (ref "R71") (pin "1") (pinfunction "1_1") (pintype "passive"))
      (node (ref "R74") (pin "2") (pinfunction "2_2") (pintype "passive"))
    )
    (net (code "147") (name "Net-(R71-Pad2)") (class "Default")
      (node (ref "R71") (pin "2") (pinfunction "2_2") (pintype "passive"))
      (node (ref "R73") (pin "1") (pinfunction "1_1") (pintype "passive"))
    )
    (net (code "148") (name "Net-(R72-Pad1)") (class "Default")
      (node (ref "R72") (pin "1") (pinfunction "1_1") (pintype "passive"))
      (node (ref "R75") (pin "2") (pinfunction "2_2") (pintype "passive"))
    )
    (net (code "149") (name "Net-(R72-Pad2)") (class "Default")
      (node (ref "R72") (pin "2") (pinfunction "2_2") (pintype "passive"))
      (node (ref "R74") (pin "1") (pinfunction "1_1") (pintype "passive"))
    )
    (net (code "150") (name "Net-(R78-Pad1)") (class "Default")
      (node (ref "R78") (pin "1") (pinfunction "1_1") (pintype "passive"))
      (node (ref "R81") (pin "2") (pinfunction "2_2") (pintype "passive"))
    )
    (net (code "151") (name "Net-(R81-Pad1)") (class "Default")
      (node (ref "R81") (pin "1") (pinfunction "1_1") (pintype "passive"))
      (node (ref "R86") (pin "2") (pinfunction "2_2") (pintype "passive"))
    )
    (net (code "152") (name "Net-(R82-Pad2)") (class "Default")
      (node (ref "R82") (pin "2") (pinfunction "2_2") (pintype "passive"))
      (node (ref "R83") (pin "1") (pinfunction "1_1") (pintype "passive"))
    )
    (net (code "153") (name "Net-(R100-Pad2)") (class "Default")
      (node (ref "R100") (pin "2") (pinfunction "2_2") (pintype "passive"))
      (node (ref "R99") (pin "1") (pinfunction "1_1") (pintype "passive"))
    )
    (net (code "154") (name "Net-(R106-Pad2)") (class "Default")
      (node (ref "R106") (pin "2") (pinfunction "2_2") (pintype "passive"))
      (node (ref "U8") (pin "1") (pinfunction "1_1") (pintype "passive"))
    )
    (net (code "155") (name "Net-(R107-Pad2)") (class "Default")
      (node (ref "R107") (pin "2") (pinfunction "2_2") (pintype "passive"))
      (node (ref "R108") (pin "2") (pinfunction "2_2") (pintype "passive"))
    )
    (net (code "156") (name "Net-(R111-Pad2)") (class "Default")
      (node (ref "R111") (pin "2") (pinfunction "2_2") (pintype "passive"))
      (node (ref "U8") (pin "4") (pinfunction "4_4") (pintype "passive"))
    )
    (net (code "157") (name "Net-(R115-Pad2)") (class "Default")
      (node (ref "R115") (pin "2") (pinfunction "2_2") (pintype "passive"))
      (node (ref "R116") (pin "1") (pinfunction "1_1") (pintype "passive"))
    )
    (net (code "158") (name "Net-(R131-Pad2)") (class "Default")
      (node (ref "R131") (pin "2") (pinfunction "2_2") (pintype "passive"))
      (node (ref "R137") (pin "2") (pinfunction "2_2") (pintype "passive"))
    )
    (net (code "159") (name "Net-(R132-Pad2)") (class "Default")
      (node (ref "R132") (pin "2") (pinfunction "2_2") (pintype "passive"))
      (node (ref "R133") (pin "2") (pinfunction "2_2") (pintype "passive"))
    )
    (net (code "160") (name "Net-(R133-Pad1)") (class "Default")
      (node (ref "R133") (pin "1") (pinfunction "1_1") (pintype "passive"))
      (node (ref "R134") (pin "1") (pinfunction "1_1") (pintype "passive"))
    )
    (net (code "161") (name "Net-(R134-Pad2)") (class "Default")
      (node (ref "R134") (pin "2") (pinfunction "2_2") (pintype "passive"))
      (node (ref "R135") (pin "2") (pinfunction "2_2") (pintype "passive"))
    )
    (net (code "162") (name "Net-(R137-Pad1)") (class "Default")
      (node (ref "R137") (pin "1") (pinfunction "1_1") (pintype "passive"))
      (node (ref "R138") (pin "1") (pinfunction "1_1") (pintype "passive"))
    )
    (net (code "163") (name "Net-(R138-Pad2)") (class "Default")
      (node (ref "R138") (pin "2") (pinfunction "2_2") (pintype "passive"))
      (node (ref "R144") (pin "2") (pinfunction "2_2") (pintype "passive"))
    )
    (net (code "164") (name "Net-(R139-Pad2)") (class "Default")
      (node (ref "R139") (pin "2") (pinfunction "2_2") (pintype "passive"))
      (node (ref "R140") (pin "2") (pinfunction "2_2") (pintype "passive"))
    )
    (net (code "165") (name "Net-(R140-Pad1)") (class "Default")
      (node (ref "R140") (pin "1") (pinfunction "1_1") (pintype "passive"))
      (node (ref "R141") (pin "1") (pinfunction "1_1") (pintype "passive"))
    )
    (net (code "166") (name "Net-(R141-Pad2)") (class "Default")
      (node (ref "R141") (pin "2") (pinfunction "2_2") (pintype "passive"))
      (node (ref "R142") (pin "2") (pinfunction "2_2") (pintype "passive"))
    )
    (net (code "167") (name "Net-(U1-IN1)") (class "Default")
      (node (ref "R9") (pin "1") (pinfunction "1_1") (pintype "passive"))
      (node (ref "U1") (pin "1") (pinfunction "IN1_1") (pintype "passive"))
    )
    (net (code "168") (name "Net-(U1-IN2)") (class "Default")
      (node (ref "R11") (pin "1") (pinfunction "1_1") (pintype "passive"))
      (node (ref "U1") (pin "2") (pinfunction "IN2_2") (pintype "passive"))
    )
    (net (code "169") (name "Net-(U1-IN3)") (class "Default")
      (node (ref "R12") (pin "1") (pinfunction "1_1") (pintype "passive"))
      (node (ref "U1") (pin "3") (pinfunction "IN3_3") (pintype "passive"))
    )
    (net (code "170") (name "Net-(U1-IN4)") (class "Default")
      (node (ref "R18") (pin "1") (pinfunction "1_1") (pintype "passive"))
      (node (ref "U1") (pin "4") (pinfunction "IN4_4") (pintype "passive"))
    )
    (net (code "171") (name "Net-(U1-IN5)") (class "Default")
      (node (ref "R21") (pin "1") (pinfunction "1_1") (pintype "passive"))
      (node (ref "U1") (pin "5") (pinfunction "IN5_5") (pintype "passive"))
    )
    (net (code "172") (name "Net-(U1-IN6)") (class "Default")
      (node (ref "R39") (pin "1") (pinfunction "1_1") (pintype "passive"))
      (node (ref "U1") (pin "6") (pinfunction "IN6_6") (pintype "passive"))
    )
    (net (code "173") (name "Net-(U1-IN7)") (class "Default")
      (node (ref "R51") (pin "1") (pinfunction "1_1") (pintype "passive"))
      (node (ref "U1") (pin "7") (pinfunction "IN7_7") (pintype "passive"))
    )
    (net (code "174") (name "Net-(U2-In)") (class "Default")
      (node (ref "*1") (pin "1") (pinfunction "1_1") (pintype "passive"))
      (node (ref "C10") (pin "1") (pinfunction "1_1") (pintype "passive"))
      (node (ref "C11") (pin "1") (pinfunction "1_1") (pintype "passive"))
      (node (ref "R13") (pin "1") (pinfunction "1_1") (pintype "passive"))
      (node (ref "R20") (pin "1") (pinfunction "1_1") (pintype "passive"))
      (node (ref "U2") (pin "1") (pinfunction "In_1") (pintype "passive"))
    )
    (net (code "175") (name "Net-(U2-Out)") (class "Default")
      (node (ref "K1") (pin "1") (pinfunction "1_1") (pintype "passive"))
      (node (ref "U2") (pin "2") (pinfunction "Out_2") (pintype "passive"))
    )
    (net (code "176") (name "Net-(U2-Vfef)") (class "Default")
      (node (ref "R7") (pin "2") (pinfunction "2_2") (pintype "passive"))
      (node (ref "U2") (pin "11") (pinfunction "Vfef_11") (pintype "passive"))
    )
    (net (code "177") (name "Net-(U2-Vout)") (class "Default")
      (node (ref "R6") (pin "2") (pinfunction "2_2") (pintype "passive"))
      (node (ref "U2") (pin "12") (pinfunction "Vout_12") (pintype "passive"))
    )
    (net (code "178") (name "Net-(U5-BBA)") (class "Default")
      (node (ref "C59") (pin "2") (pinfunction "2_2") (pintype "passive"))
      (node (ref "R86") (pin "1") (pinfunction "1_1") (pintype "passive"))
      (node (ref "R98") (pin "2") (pinfunction "2_2") (pintype "passive"))
      (node (ref "U5") (pin "1") (pinfunction "BBA_1") (pintype "passive"))
    )
    (net (code "179") (name "Net-(U5-CS)") (class "Default")
      (node (ref "R93") (pin "1") (pinfunction "1_1") (pintype "passive"))
      (node (ref "R94") (pin "1") (pinfunction "1_1") (pintype "passive"))
      (node (ref "U5") (pin "3") (pinfunction "CS_3") (pintype "passive"))
    )
    (net (code "180") (name "Net-(U5-FBB)") (class "Default")
      (node (ref "C76") (pin "2") (pinfunction "2_2") (pintype "passive"))
      (node (ref "R111") (pin "1") (pinfunction "1_1") (pintype "passive"))
      (node (ref "U5") (pin "2") (pinfunction "FBB_2") (pintype "passive"))
    )
    (net (code "181") (name "Net-(U5-VCC)") (class "Default")
      (node (ref "C57") (pin "1") (pinfunction "1_1") (pintype "passive"))
      (node (ref "C60") (pin "1") (pinfunction "1_1") (pintype "passive"))
      (node (ref "C61") (pin "1") (pinfunction "1_1") (pintype "passive"))
      (node (ref "R89") (pin "2") (pinfunction "2_2") (pintype "passive"))
      (node (ref "U5") (pin "7") (pinfunction "VCC_7") (pintype "power_in"))
    )
    (net (code "182") (name "Net-(U6-CURRENT_SENSE)") (class "Default")
      (node (ref "C77") (pin "2") (pinfunction "2_2") (pintype "passive"))
      (node (ref "C83") (pin "1") (pinfunction "1_1") (pintype "passive"))
      (node (ref "R110") (pin "2") (pinfunction "2_2") (pintype "passive"))
      (node (ref "U6") (pin "3") (pinfunction "CURRENT_SENSE_3") (pintype "input"))
    )
    (net (code "183") (name "Net-(U6-OUT)") (class "Default")
      (node (ref "D24") (pin "1") (pinfunction "C_1") (pintype "passive"))
      (node (ref "D24") (pin "2") (pinfunction "C_2") (pintype "passive"))
      (node (ref "R103") (pin "2") (pinfunction "2_2") (pintype "passive"))
      (node (ref "U6") (pin "6") (pinfunction "OUT_6") (pintype "output"))
    )
    (net (code "184") (name "Net-(U6-RT{slash}CT)") (class "Default")
      (node (ref "C79") (pin "2") (pinfunction "2_2") (pintype "passive"))
      (node (ref "C83") (pin "2") (pinfunction "2_2") (pintype "passive"))
      (node (ref "R112") (pin "1") (pinfunction "1_1") (pintype "passive"))
      (node (ref "U6") (pin "4") (pinfunction "RT/CT_4") (pintype "input"))
    )
    (net (code "185") (name "Net-(U6-VCC)") (class "Default")
      (node (ref "C69") (pin "1") (pinfunction "1_1") (pintype "passive"))
      (node (ref "C72") (pin "2") (pinfunction "2_2") (pintype "passive"))
      (node (ref "J4") (pin "1") (pinfunction "1_1") (pintype "passive"))
      (node (ref "R95") (pin "2") (pinfunction "2_2") (pintype "passive"))
      (node (ref "U6") (pin "7") (pinfunction "VCC_7") (pintype "power_in"))
    )
    (net (code "186") (name "Net-(U6-VOLTAGE_FB)") (class "Default")
      (node (ref "C74") (pin "2") (pinfunction "2_2") (pintype "passive"))
      (node (ref "R118") (pin "1") (pinfunction "1_1") (pintype "passive"))
      (node (ref "U6") (pin "2") (pinfunction "VOLTAGE_FB_2") (pintype "input"))
    )
    (net (code "187") (name "Net-(U6-VREF)") (class "Default")
      (node (ref "C78") (pin "2") (pinfunction "2_2") (pintype "passive"))
      (node (ref "D26") (pin "2") (pinfunction "C_2") (pintype "passive"))
      (node (ref "R112") (pin "2") (pinfunction "2_2") (pintype "passive"))
      (node (ref "R136") (pin "1") (pinfunction "1_1") (pintype "passive"))
      (node (ref "U6") (pin "8") (pinfunction "VREF_8") (pintype "output"))
    )
    (net (code "188") (name "Net-(U7-+INA)") (class "Default")
      (node (ref "C81") (pin "1") (pinfunction "1_1") (pintype "passive"))
      (node (ref "R116") (pin "2") (pinfunction "2_2") (pintype "passive"))
      (node (ref "R126") (pin "1") (pinfunction "1_1") (pintype "passive"))
      (node (ref "U7") (pin "3") (pinfunction "+INA_3") (pintype "input"))
    )
    (net (code "189") (name "Net-(U7--INA)") (class "Default")
      (node (ref "C71") (pin "1") (pinfunction "1_1") (pintype "passive"))
      (node (ref "R105") (pin "1") (pinfunction "1_1") (pintype "passive"))
      (node (ref "R108") (pin "1") (pinfunction "1_1") (pintype "passive"))
      (node (ref "U7") (pin "2") (pinfunction "-INA_2") (pintype "input"))
    )
    (net (code "190") (name "Net-(U7--INB)") (class "Default")
      (node (ref "U7") (pin "6") (pinfunction "-INB_6") (pintype "input"))
      (node (ref "U7") (pin "7") (pinfunction "OUTB_7") (pintype "output"))
    )
    (net (code "191") (name "Net-(U7-OUTA)") (class "Default")
      (node (ref "C71") (pin "2") (pinfunction "2_2") (pintype "passive"))
      (node (ref "R102") (pin "1") (pinfunction "1_1") (pintype "passive"))
      (node (ref "R105") (pin "2") (pinfunction "2_2") (pintype "passive"))
      (node (ref "U7") (pin "1") (pinfunction "OUTA_1") (pintype "output"))
    )
    (net (code "192") (name "Net-(U9-+)") (class "Default")
      (node (ref "C80") (pin "1") (pinfunction "1_1") (pintype "passive"))
      (node (ref "R113") (pin "2") (pinfunction "2_2") (pintype "passive"))
      (node (ref "R124") (pin "1") (pinfunction "1_1") (pintype "passive"))
      (node (ref "U8") (pin "2") (pinfunction "2_2") (pintype "passive"))
      (node (ref "U9") (pin "1") (pinfunction "+_1") (pintype "passive"))
    )
    (net (code "193") (name "Net-(U9-adj)") (class "Default")
      (node (ref "C84") (pin "2") (pinfunction "2_2") (pintype "passive"))
      (node (ref "R100") (pin "1") (pinfunction "1_1") (pintype "passive"))
      (node (ref "R128") (pin "2") (pinfunction "2_2") (pintype "passive"))
      (node (ref "R129") (pin "2") (pinfunction "2_2") (pintype "passive"))
      (node (ref "R97") (pin "2") (pinfunction "2_2") (pintype "passive"))
      (node (ref "U9") (pin "2") (pinfunction "adj_2") (pintype "passive"))
    )
    (net (code "194") (name "Net-(U10-In)") (class "Default")
      (node (ref "C86") (pin "2") (pinfunction "2_2") (pintype "passive"))
      (node (ref "C89") (pin "2") (pinfunction "2_2") (pintype "passive"))
      (node (ref "L10") (pin "2") (pinfunction "2_2") (pintype "passive"))
      (node (ref "U10") (pin "1") (pinfunction "In_1") (pintype "passive"))
    )
    (net (code "195") (name "Net-(U10-Out)") (class "Default")
      (node (ref "*14") (pin "1") (pinfunction "1_1") (pintype "passive"))
      (node (ref "R135") (pin "1") (pinfunction "1_1") (pintype "passive"))
      (node (ref "U10") (pin "2") (pinfunction "Out_2") (pintype "passive"))
    )
    (net (code "196") (name "Net-(U10-Vfef)") (class "Default")
      (node (ref "R107") (pin "1") (pinfunction "1_1") (pintype "passive"))
      (node (ref "U10") (pin "11") (pinfunction "Vfef_11") (pintype "passive"))
    )
    (net (code "197") (name "Net-(U10-Vout)") (class "Default")
      (node (ref "R115") (pin "1") (pinfunction "1_1") (pintype "passive"))
      (node (ref "U10") (pin "12") (pinfunction "Vout_12") (pintype "passive"))
    )
    (net (code "198") (name "Net-(V1-B)") (class "Default")
      (node (ref "R80") (pin "2") (pinfunction "2_2") (pintype "passive"))
      (node (ref "V1") (pin "1") (pinfunction "B_1") (pintype "passive"))
    )
    (net (code "199") (name "Net-(V1-C)") (class "Default")
      (node (ref "H1") (pin "1") (pinfunction "1_1") (pintype "passive"))
      (node (ref "R76") (pin "1") (pinfunction "1_1") (pintype "passive"))
      (node (ref "V1") (pin "2") (pinfunction "C_2") (pintype "passive"))
    )
    (net (code "200") (name "Net-(V2-B)") (class "Default")
      (node (ref "R114") (pin "2") (pinfunction "2_2") (pintype "passive"))
      (node (ref "V2") (pin "1") (pinfunction "B_1") (pintype "passive"))
    )
    (net (code "201") (name "Net-(V2-C)") (class "Default")
      (node (ref "H2") (pin "1") (pinfunction "1_1") (pintype "passive"))
      (node (ref "R101") (pin "1") (pinfunction "1_1") (pintype "passive"))
      (node (ref "V2") (pin "2") (pinfunction "C_2") (pintype "passive"))
    )
    (net (code "202") (name "unconnected-(D10-A-Pad1)") (class "Default")
      (node (ref "D10") (pin "1") (pinfunction "A_1") (pintype "passive+no_connect"))
    )
    (net (code "203") (name "unconnected-(D22-NC-Pad2)") (class "Default")
      (node (ref "D22") (pin "2") (pinfunction "NC_2") (pintype "passive+no_connect"))
    )
    (net (code "204") (name "unconnected-(D25-NC-Pad2)") (class "Default")
      (node (ref "D25") (pin "2") (pinfunction "NC_2") (pintype "passive+no_connect"))
    )
    (net (code "205") (name "unconnected-(D27-NC-Pad2)") (class "Default")
      (node (ref "D27") (pin "2") (pinfunction "NC_2") (pintype "passive+no_connect"))
    )
    (net (code "206") (name "unconnected-(J5-Pad3)") (class "Default")
      (node (ref "J5") (pin "3") (pinfunction "3_3") (pintype "passive"))
    )
    (net (code "207") (name "unconnected-(J5-Pad20)") (class "Default")
      (node (ref "J5") (pin "20") (pinfunction "20_20") (pintype "passive+no_connect"))
    )
    (net (code "208") (name "unconnected-(K2-Pad3)") (class "Default")
      (node (ref "K2") (pin "3") (pinfunction "3_3") (pintype "passive+no_connect"))
    )
    (net (code "209") (name "unconnected-(K2-Pad10)") (class "Default")
      (node (ref "K2") (pin "10") (pinfunction "10_10") (pintype "passive+no_connect"))
    )
    (net (code "210") (name "unconnected-(L7-Pad1)") (class "Default")
      (node (ref "L7") (pin "1") (pinfunction "1_1") (pintype "passive+no_connect"))
    )
    (net (code "211") (name "unconnected-(R143-Pad1)") (class "Default")
      (node (ref "R143") (pin "1") (pinfunction "1_1") (pintype "passive+no_connect"))
    )
    (net (code "212") (name "unconnected-(R146-Pad1)") (class "Default")
      (node (ref "R146") (pin "1") (pinfunction "1_1") (pintype "passive+no_connect"))
    )
    (net (code "213") (name "unconnected-(R147-Pad2)") (class "Default")
      (node (ref "R147") (pin "2") (pinfunction "2_2") (pintype "passive+no_connect"))
    )
    (net (code "214") (name "unconnected-(U5-NC-Pad4)") (class "Default")
      (node (ref "U5") (pin "4") (pinfunction "NC_4") (pintype "passive+no_connect"))
    )
  )
)
